# ESP32_Display_2_1_K__Main_V1_0.net
KiCad netlist of a schematic drawn in EAGLE
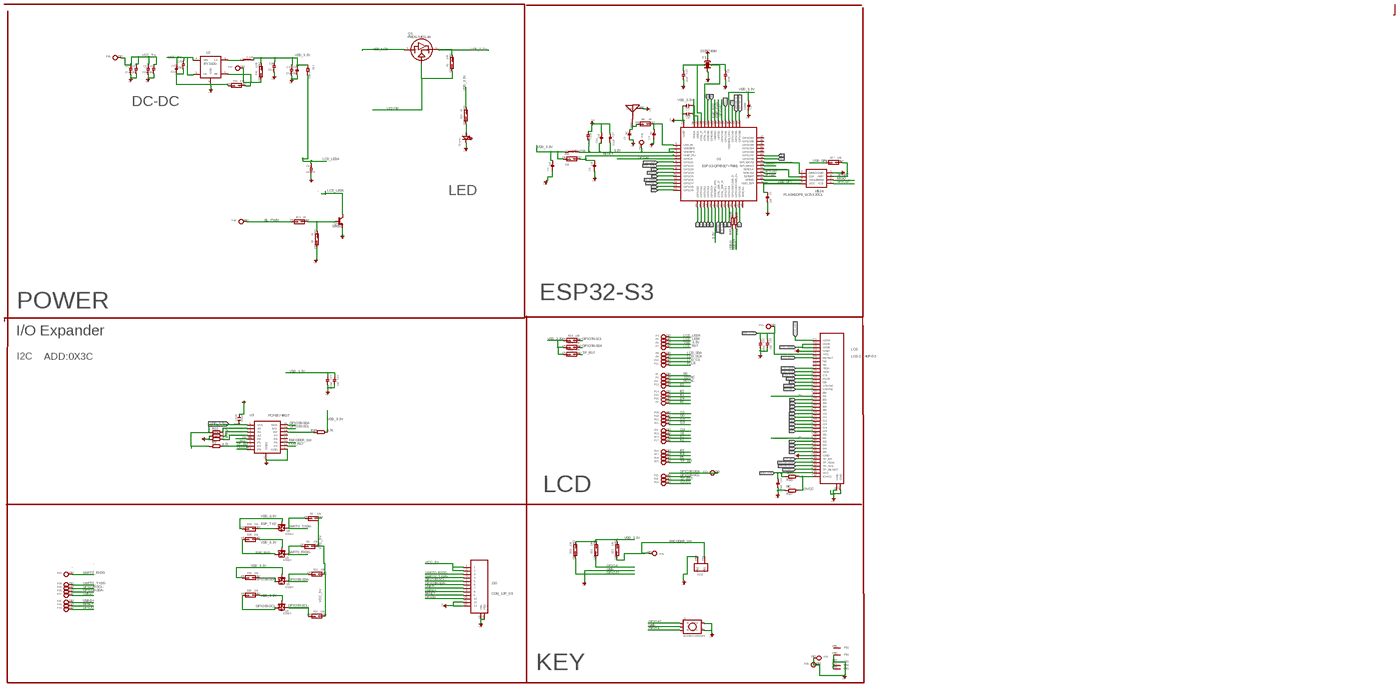
[diagram p0: schematic, sheet 1, overview]
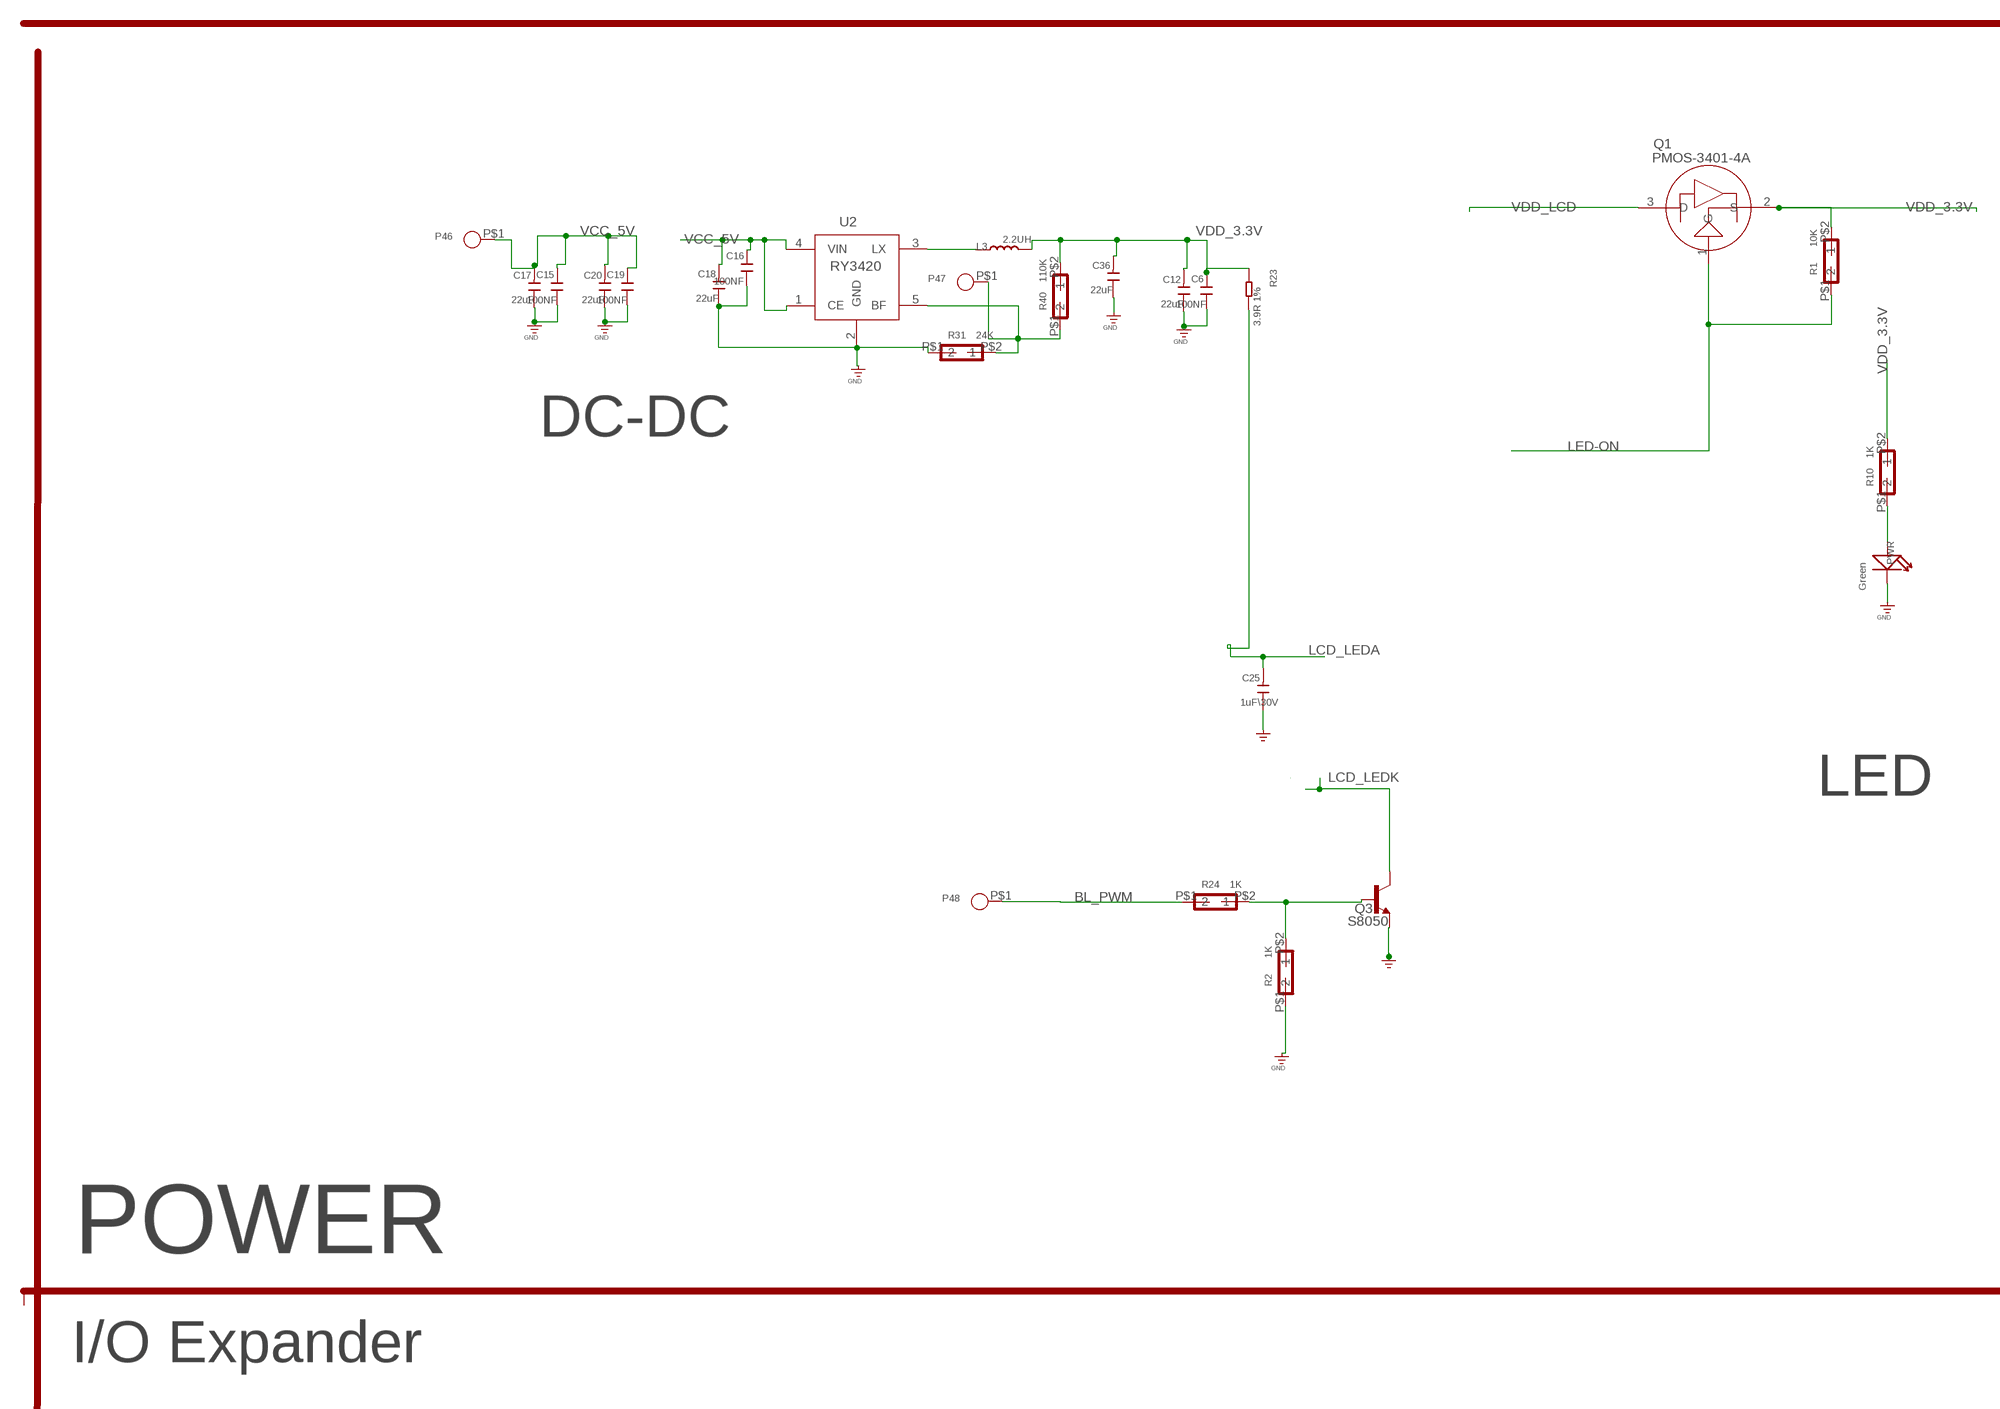
[diagram p1: schematic, sheet 1, part 1 of 5]
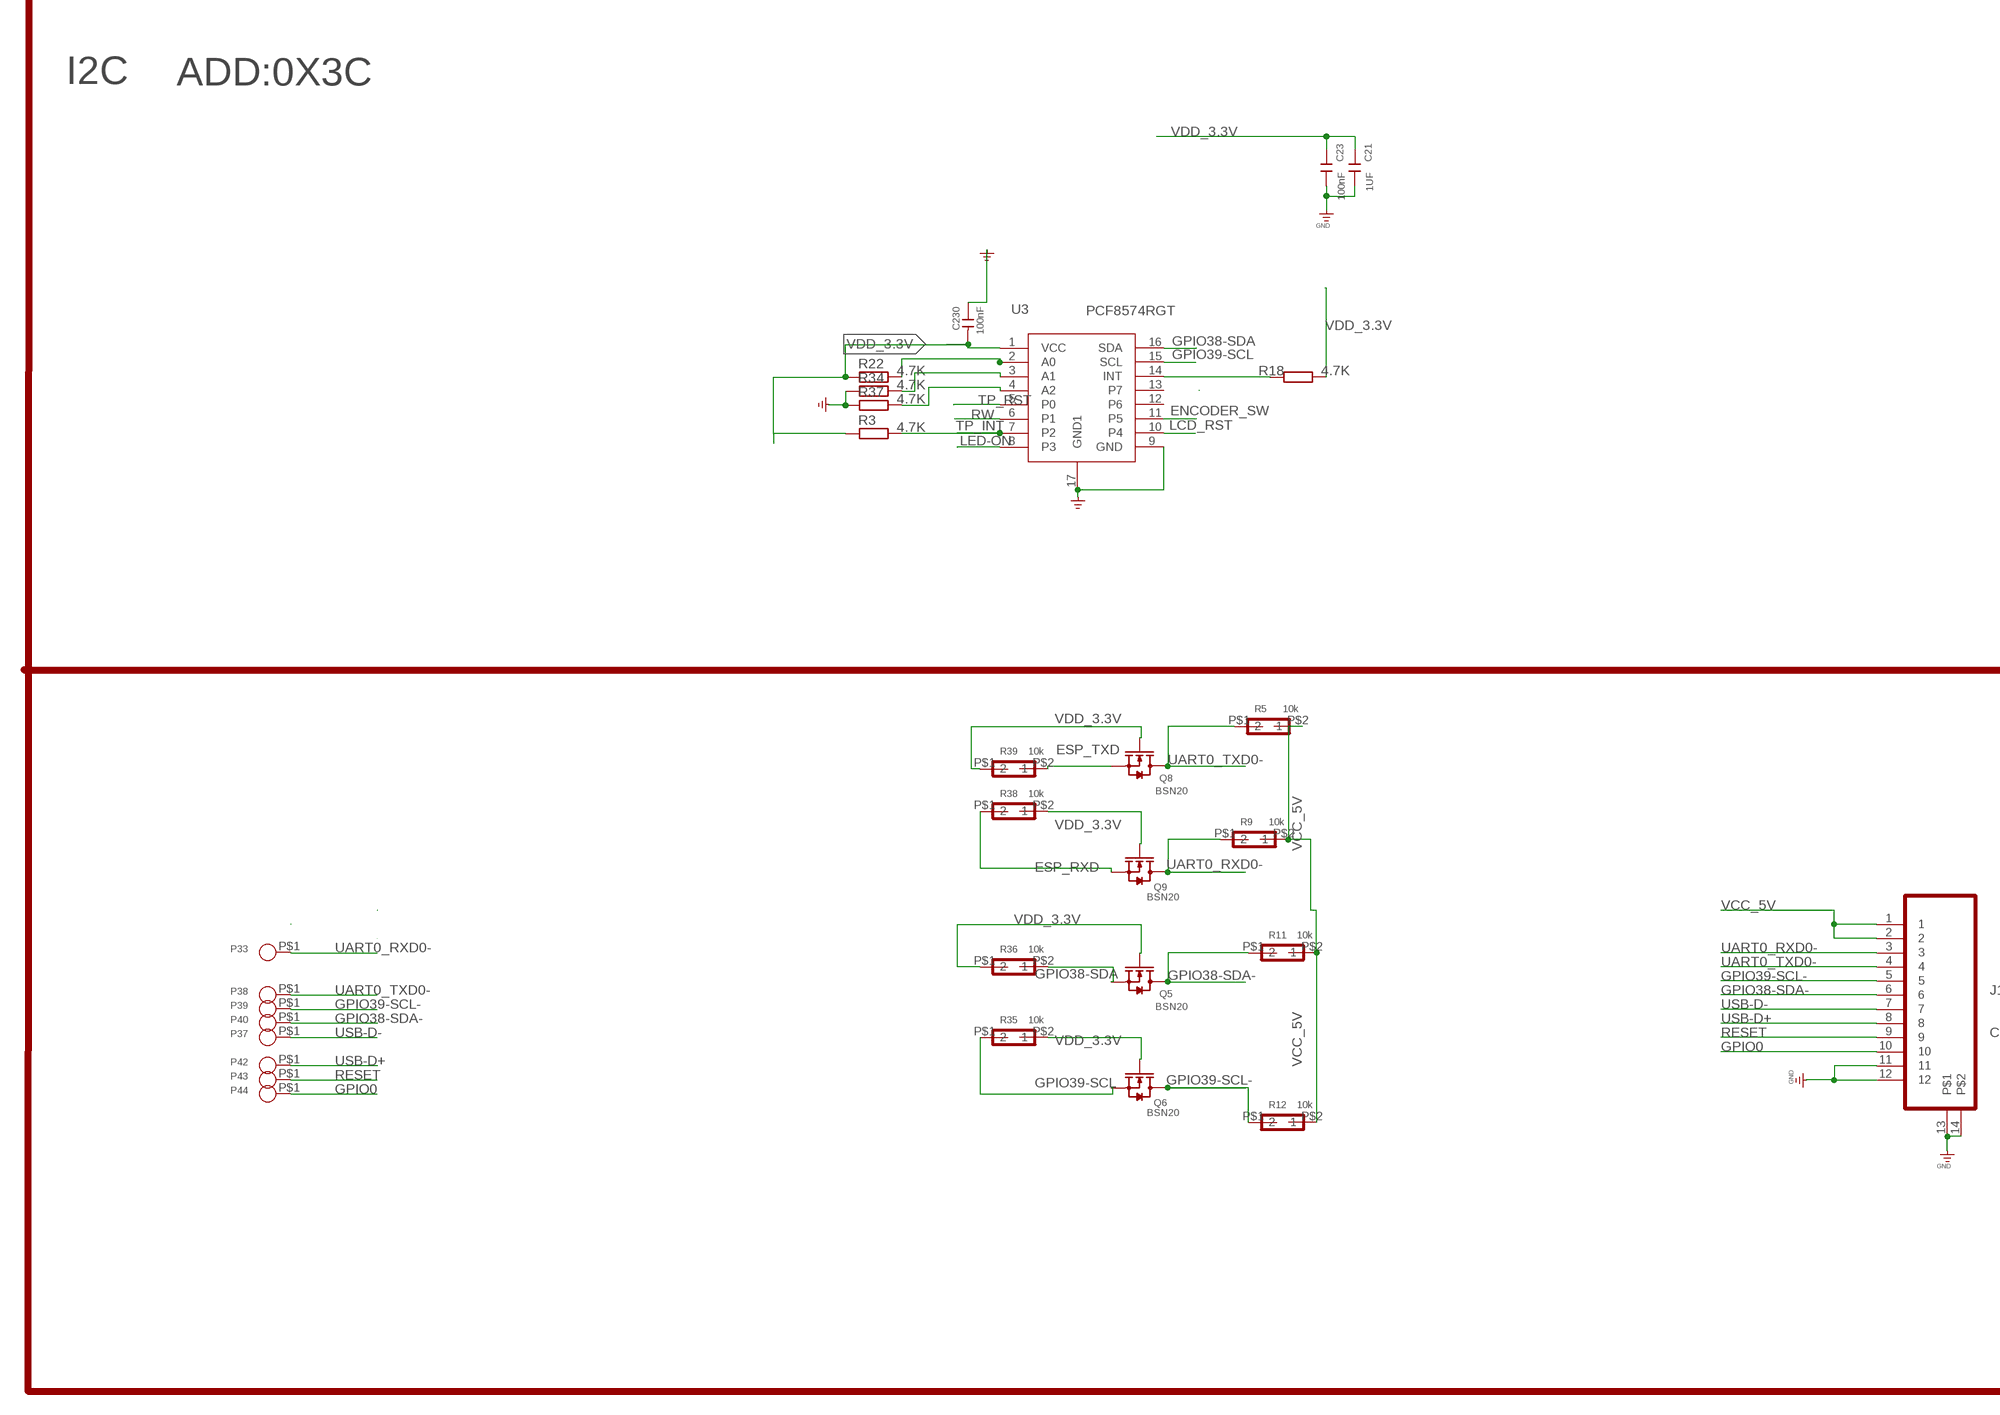
[diagram p2: schematic, sheet 1, part 2 of 5]
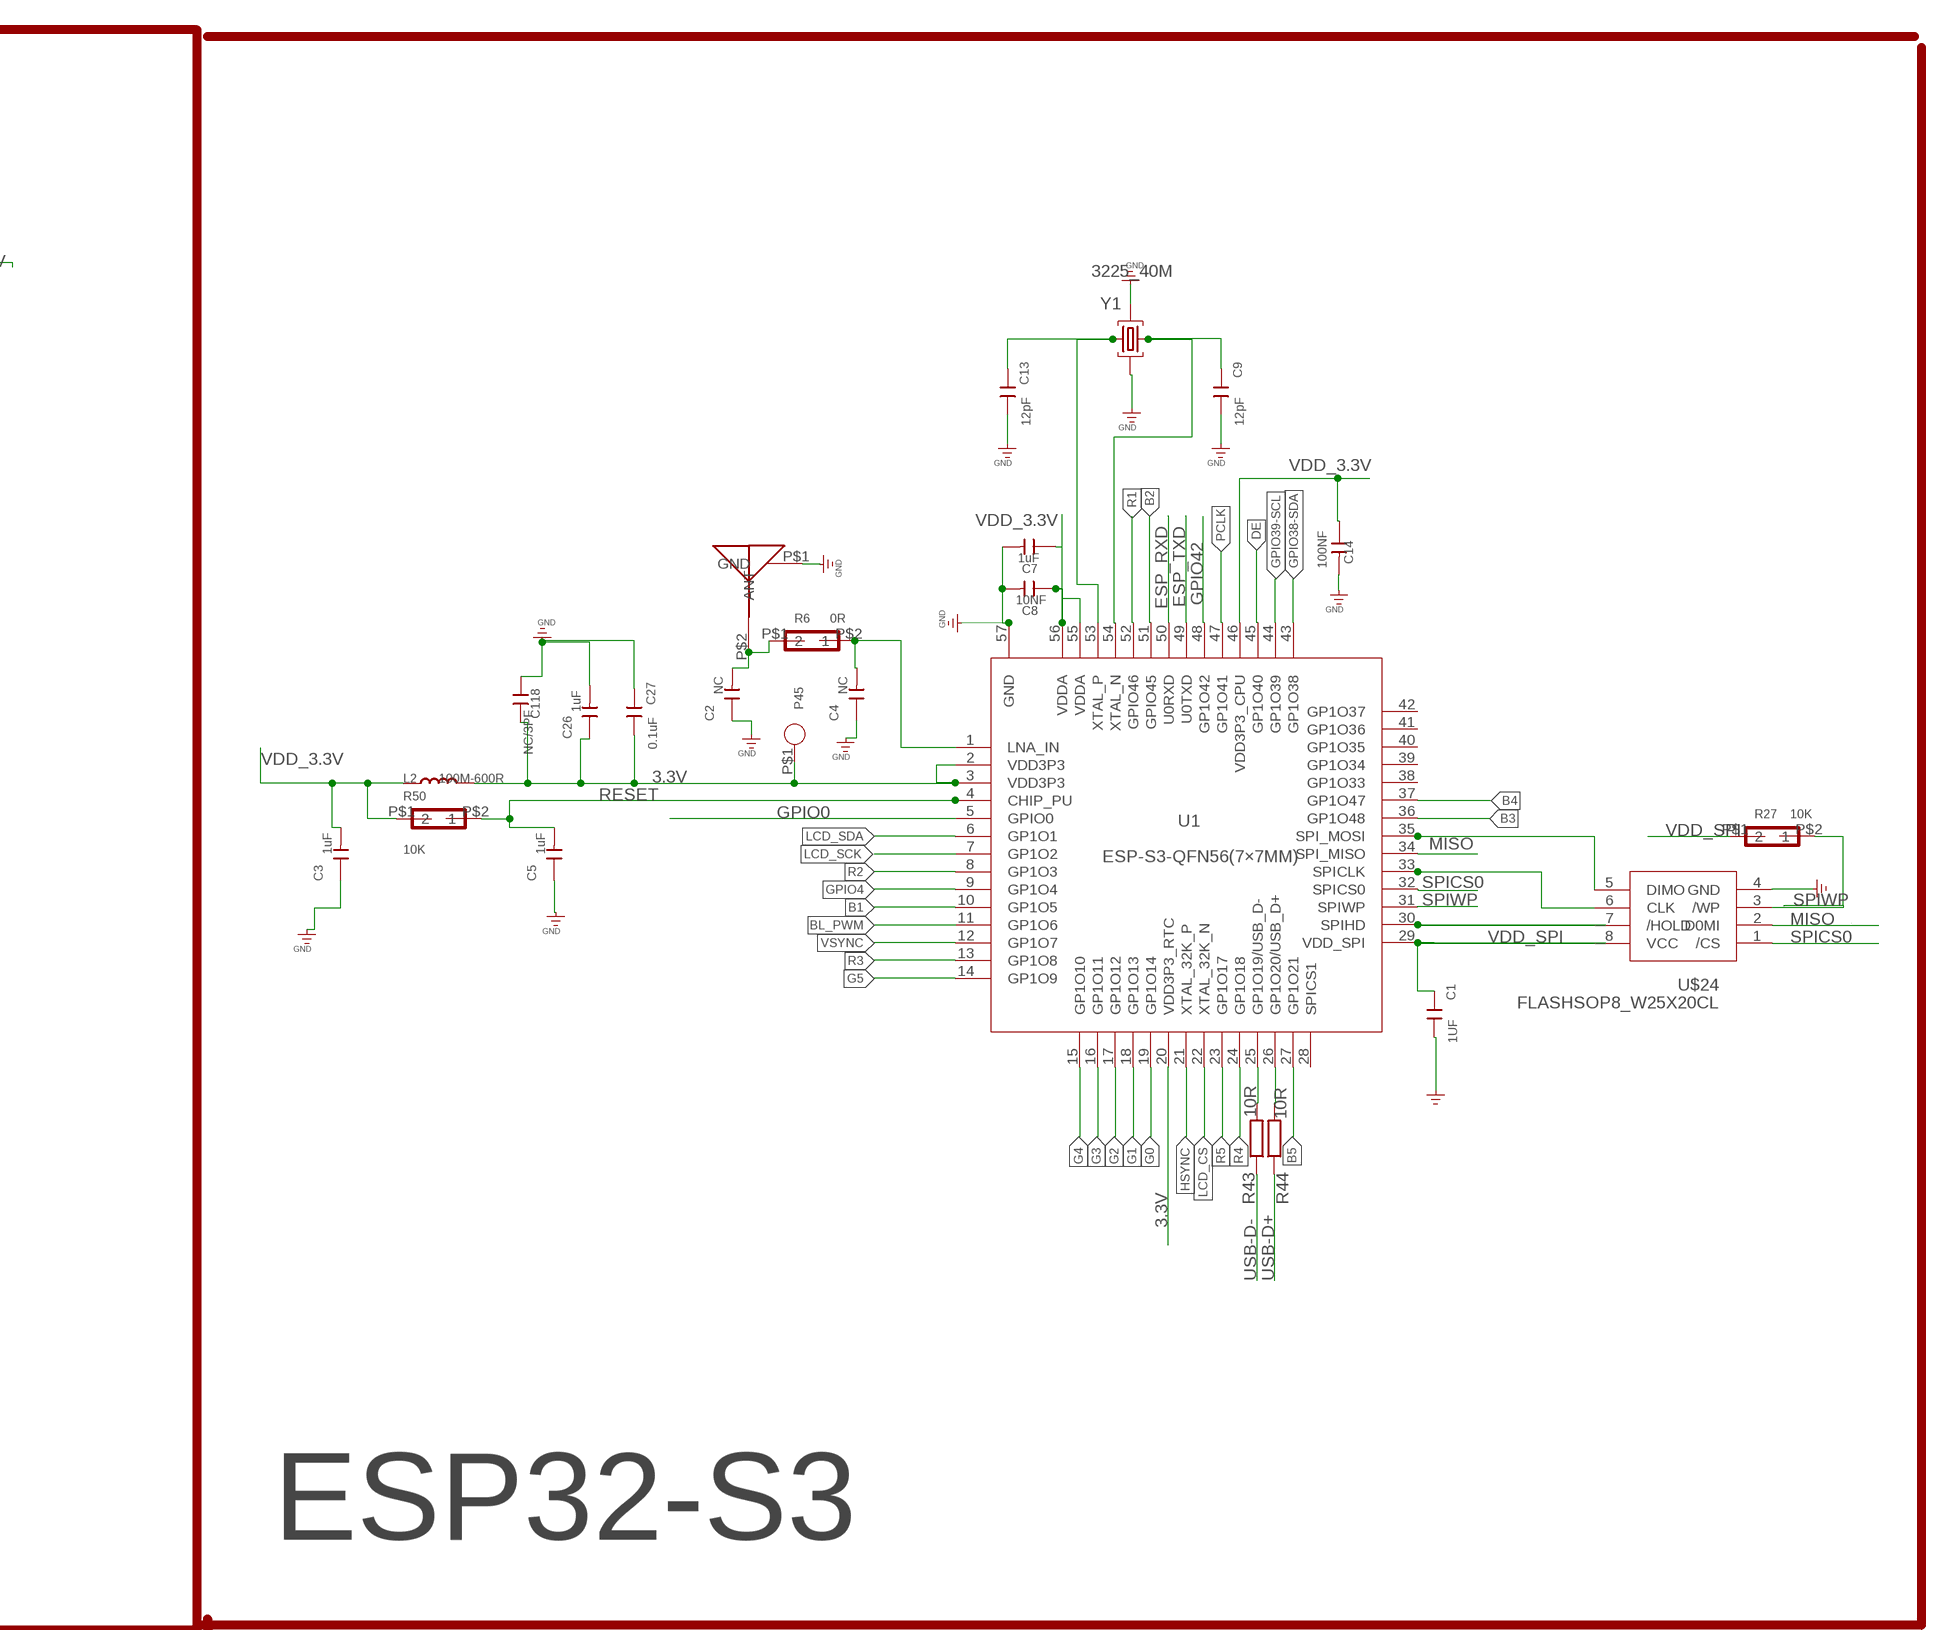
[diagram p3: schematic, sheet 1, part 3 of 5]
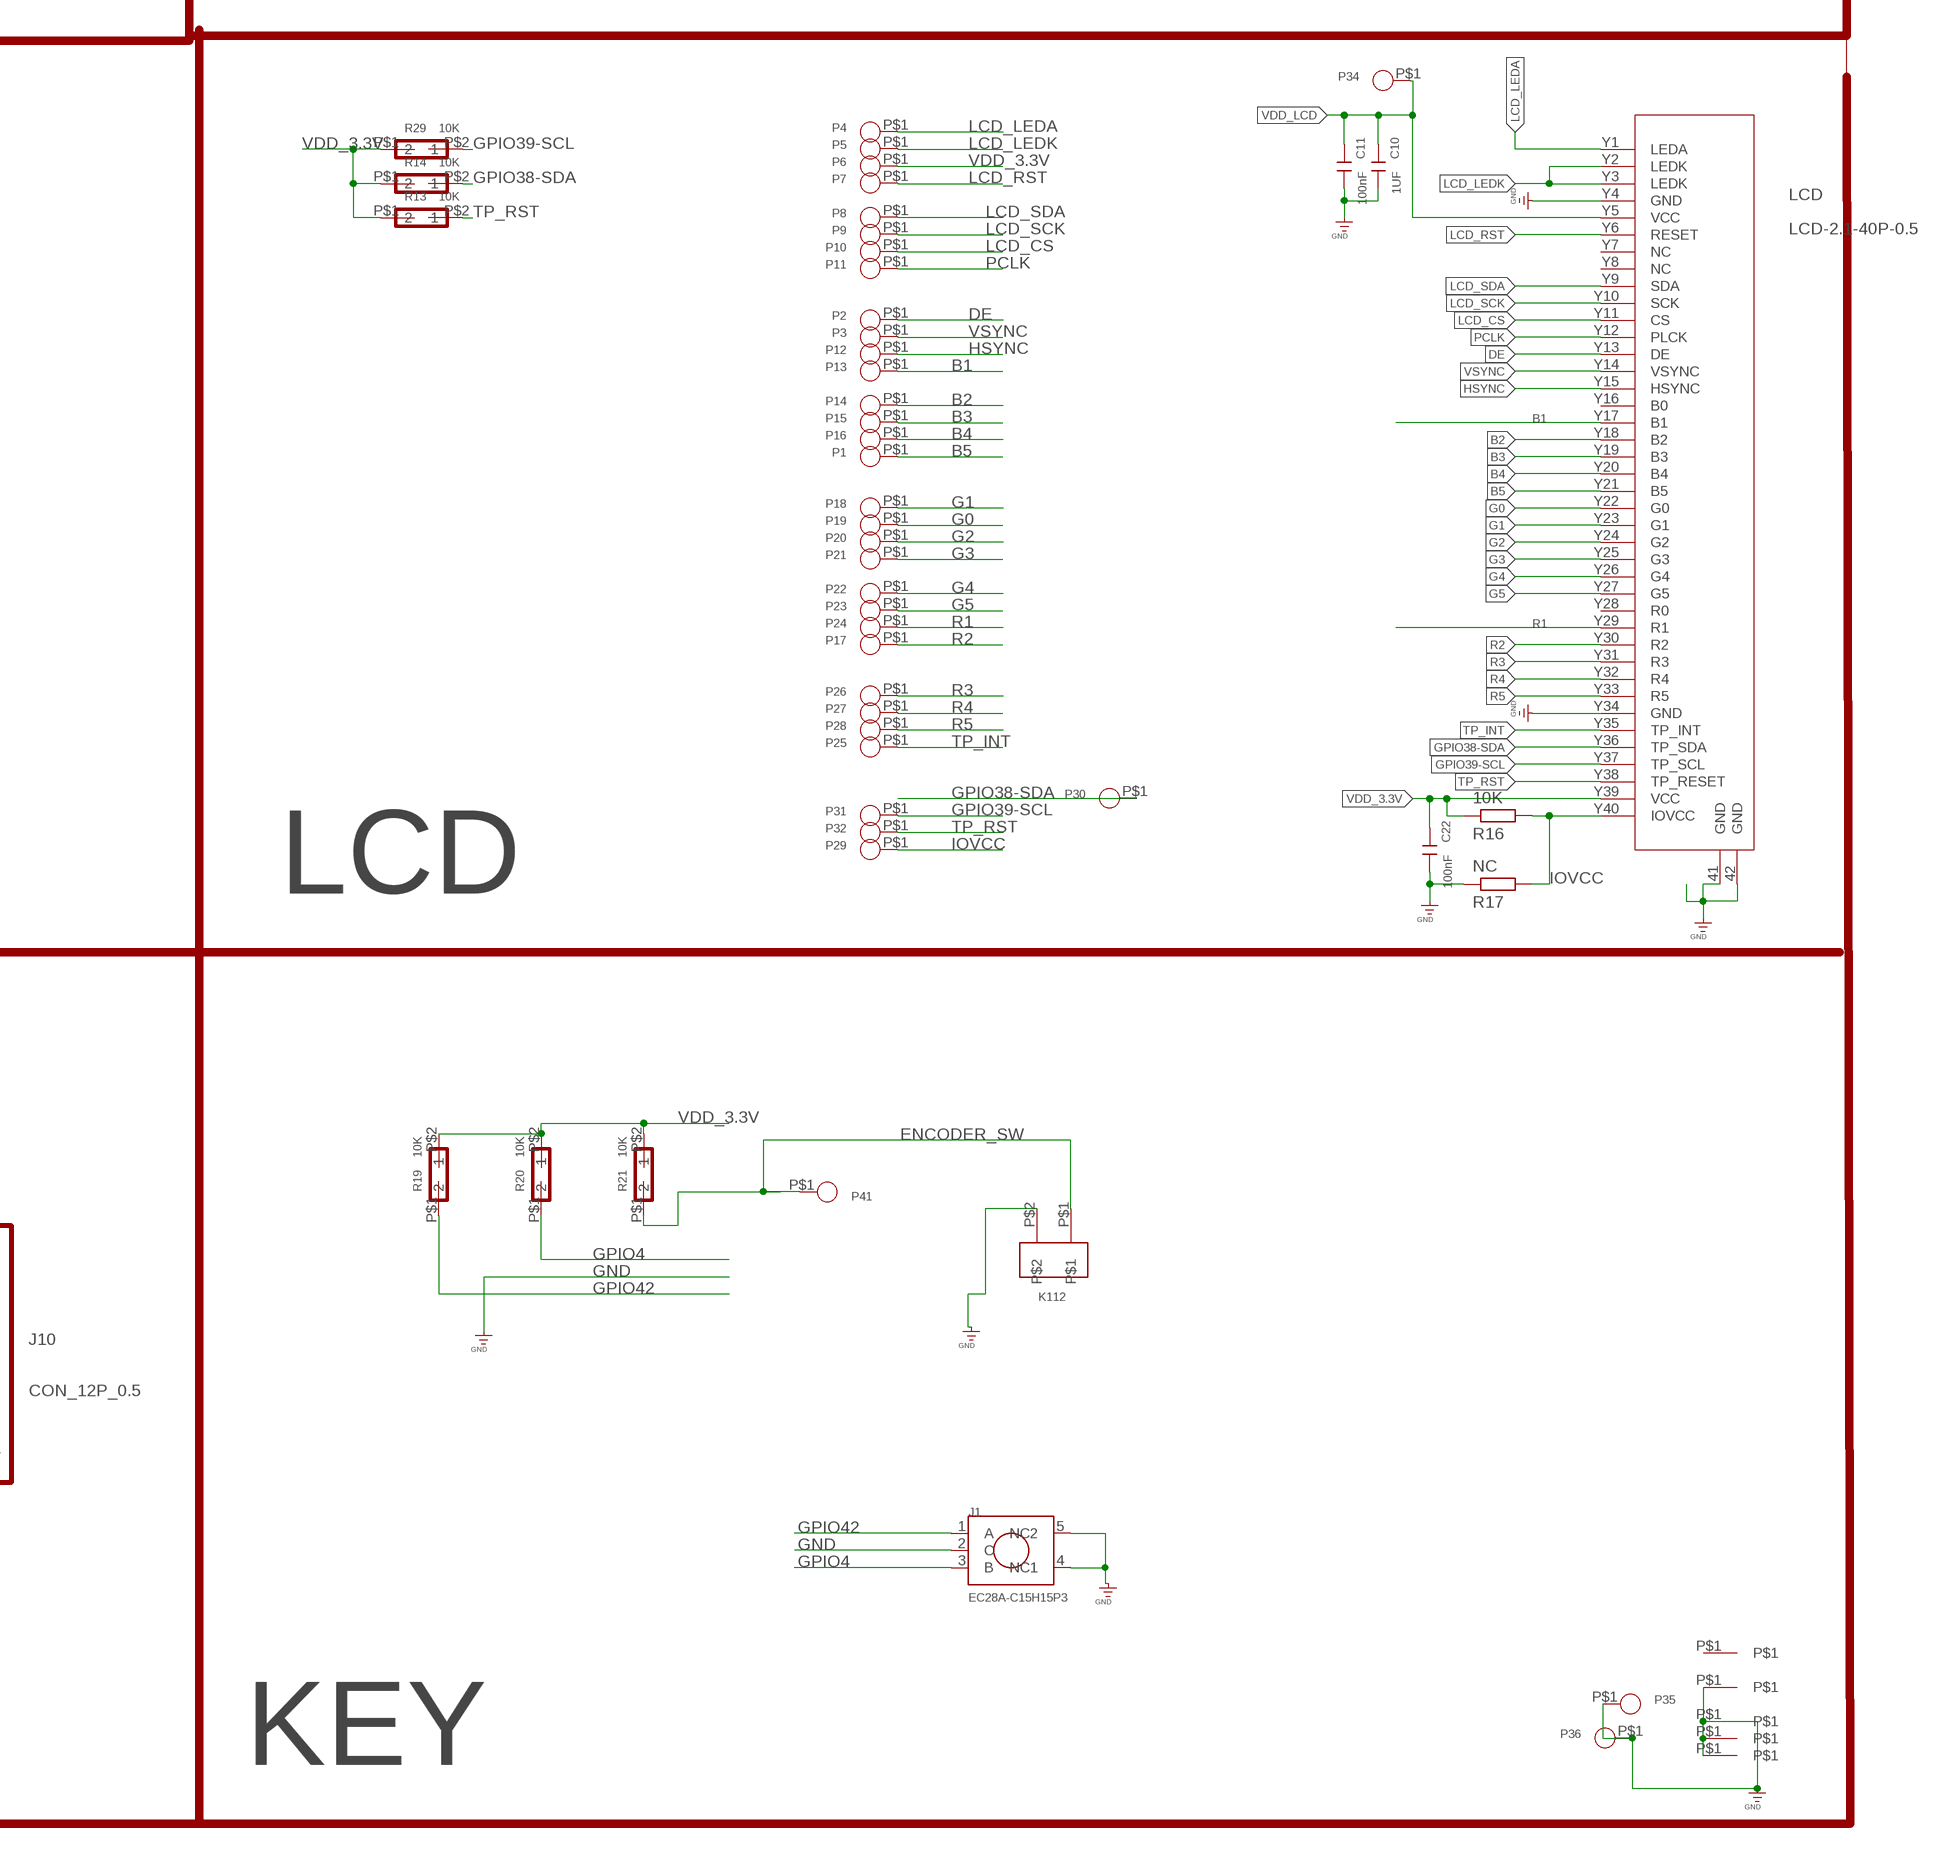
[diagram p4: schematic, sheet 1, part 4 of 5]
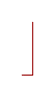
[diagram p5: schematic, sheet 1, part 5 of 5]

(export (version "E")
  (design (tool "Eeschema 10.0.6"))
  (components
    (comp (ref "ANT")
      (value "BT_ANT")
      (footprint "eagle-import:BT_ANT")
      (libsource (lib "eagle-import") (part "BT_ANT"))
    )
    (comp (ref "C1")
      (value "1UF")
      (footprint "eagle-import:0402")
      (libsource (lib "eagle-import") (part "C0402_W"))
    )
    (comp (ref "C2")
      (value "NC")
      (footprint "eagle-import:C0402")
      (libsource (lib "eagle-import") (part "CAPC0402-1"))
    )
    (comp (ref "C3")
      (value "1uF")
      (footprint "eagle-import:C0402")
      (libsource (lib "eagle-import") (part "CAPC0402-1"))
    )
    (comp (ref "C4")
      (value "NC")
      (footprint "eagle-import:C0402")
      (libsource (lib "eagle-import") (part "CAPC0402-1"))
    )
    (comp (ref "C5")
      (value "1uF")
      (footprint "eagle-import:C0402")
      (libsource (lib "eagle-import") (part "CAPC0402-1"))
    )
    (comp (ref "C6")
      (value "100NF")
      (footprint "eagle-import:0603")
      (libsource (lib "eagle-import") (part "C0603"))
    )
    (comp (ref "C7")
      (value "1uF")
      (footprint "eagle-import:C0603")
      (libsource (lib "eagle-import") (part "C-0603"))
    )
    (comp (ref "C8")
      (value "10NF")
      (footprint "eagle-import:C0603")
      (libsource (lib "eagle-import") (part "C-0603"))
    )
    (comp (ref "C9")
      (value "12pF")
      (footprint "eagle-import:0402")
      (libsource (lib "eagle-import") (part "C0402_W"))
    )
    (comp (ref "C10")
      (value "1UF")
      (footprint "eagle-import:0402")
      (libsource (lib "eagle-import") (part "C0402_W"))
    )
    (comp (ref "C11")
      (value "100nF")
      (footprint "eagle-import:0402")
      (libsource (lib "eagle-import") (part "C0402_W"))
    )
    (comp (ref "C12")
      (value "22uF")
      (footprint "eagle-import:0805")
      (libsource (lib "eagle-import") (part "C0805"))
    )
    (comp (ref "C13")
      (value "12pF")
      (footprint "eagle-import:0402")
      (libsource (lib "eagle-import") (part "C0402_W"))
    )
    (comp (ref "C14")
      (value "100NF")
      (footprint "eagle-import:C0603")
      (libsource (lib "eagle-import") (part "C-0603"))
    )
    (comp (ref "C15")
      (value "100NF")
      (footprint "eagle-import:0603")
      (libsource (lib "eagle-import") (part "C0603"))
    )
    (comp (ref "C16")
      (value "100NF")
      (footprint "eagle-import:0603")
      (libsource (lib "eagle-import") (part "C0603"))
    )
    (comp (ref "C17")
      (value "22uF")
      (footprint "eagle-import:0805")
      (libsource (lib "eagle-import") (part "C0805"))
    )
    (comp (ref "C18")
      (value "22uF")
      (footprint "eagle-import:0805")
      (libsource (lib "eagle-import") (part "C0805"))
    )
    (comp (ref "C19")
      (value "100NF")
      (footprint "eagle-import:0603")
      (libsource (lib "eagle-import") (part "C0603"))
    )
    (comp (ref "C20")
      (value "22uF")
      (footprint "eagle-import:0805")
      (libsource (lib "eagle-import") (part "C0805"))
    )
    (comp (ref "C21")
      (value "1UF")
      (footprint "eagle-import:0402")
      (libsource (lib "eagle-import") (part "C0402_W"))
    )
    (comp (ref "C22")
      (value "100nF")
      (footprint "eagle-import:0402")
      (libsource (lib "eagle-import") (part "C0402_W"))
    )
    (comp (ref "C23")
      (value "100nF")
      (footprint "eagle-import:0402")
      (libsource (lib "eagle-import") (part "C0402_W"))
    )
    (comp (ref "C25")
      (value "1uF\\30V")
      (footprint "eagle-import:0805")
      (libsource (lib "eagle-import") (part "C0805"))
    )
    (comp (ref "C26")
      (value "1uF")
      (footprint "eagle-import:C0402")
      (libsource (lib "eagle-import") (part "CAPC0402-1"))
    )
    (comp (ref "C27")
      (value "0.1uF")
      (footprint "eagle-import:0402")
      (libsource (lib "eagle-import") (part "C0402_W"))
    )
    (comp (ref "C36")
      (value "22uF")
      (footprint "eagle-import:0805")
      (libsource (lib "eagle-import") (part "C0805"))
    )
    (comp (ref "C118")
      (value "NC/3PF")
      (footprint "eagle-import:0603")
      (libsource (lib "eagle-import") (part "C0603"))
    )
    (comp (ref "C230")
      (value "100nF")
      (footprint "eagle-import:C0603")
      (libsource (lib "eagle-import") (part "CAPC0603"))
    )
    (comp (ref "J1")
      (value "EC28A-C15H15P3")
      (footprint "eagle-import:EC28A-C15H15P3")
      (libsource (lib "eagle-import") (part "EC28A-C15H15P3"))
    )
    (comp (ref "J10")
      (value "CON_12P_0.5")
      (footprint "eagle-import:0.5MM-12P")
      (libsource (lib "eagle-import") (part "CON_12P_0.5"))
    )
    (comp (ref "K112")
      (value "BUTTON_2P")
      (footprint "eagle-import:BUTTON_2P")
      (libsource (lib "eagle-import") (part "BUTTON_2P"))
    )
    (comp (ref "L2")
      (value "100M-600R")
      (footprint "eagle-import:L0603")
      (libsource (lib "eagle-import") (part "L0603"))
    )
    (comp (ref "L3")
      (value "2.2UH")
      (footprint "eagle-import:L0420")
      (libsource (lib "eagle-import") (part "LL0420"))
    )
    (comp (ref "LCD")
      (value "LCD-2.1-40P-0.5")
      (footprint "eagle-import:0.5MM-40P")
      (libsource (lib "eagle-import") (part "LCD-2.1-40P-0.5"))
    )
    (comp (ref "P1")
      (value "PADPAD-1.0MM")
      (footprint "eagle-import:PAD-1.0MM")
      (libsource (lib "eagle-import") (part "PADPAD-1.0MM"))
    )
    (comp (ref "P2")
      (value "PADPAD-1.0MM")
      (footprint "eagle-import:PAD-1.0MM")
      (libsource (lib "eagle-import") (part "PADPAD-1.0MM"))
    )
    (comp (ref "P3")
      (value "PADPAD-1.0MM")
      (footprint "eagle-import:PAD-1.0MM")
      (libsource (lib "eagle-import") (part "PADPAD-1.0MM"))
    )
    (comp (ref "P4")
      (value "PADPAD-1.0MM")
      (footprint "eagle-import:PAD-1.0MM")
      (libsource (lib "eagle-import") (part "PADPAD-1.0MM"))
    )
    (comp (ref "P5")
      (value "PADPAD-1.0MM")
      (footprint "eagle-import:PAD-1.0MM")
      (libsource (lib "eagle-import") (part "PADPAD-1.0MM"))
    )
    (comp (ref "P6")
      (value "PADPAD-1.0MM")
      (footprint "eagle-import:PAD-1.0MM")
      (libsource (lib "eagle-import") (part "PADPAD-1.0MM"))
    )
    (comp (ref "P7")
      (value "PADPAD-1.0MM")
      (footprint "eagle-import:PAD-1.0MM")
      (libsource (lib "eagle-import") (part "PADPAD-1.0MM"))
    )
    (comp (ref "P8")
      (value "PADPAD-1.0MM")
      (footprint "eagle-import:PAD-1.0MM")
      (libsource (lib "eagle-import") (part "PADPAD-1.0MM"))
    )
    (comp (ref "P9")
      (value "PADPAD-1.0MM")
      (footprint "eagle-import:PAD-1.0MM")
      (libsource (lib "eagle-import") (part "PADPAD-1.0MM"))
    )
    (comp (ref "P10")
      (value "PADPAD-1.0MM")
      (footprint "eagle-import:PAD-1.0MM")
      (libsource (lib "eagle-import") (part "PADPAD-1.0MM"))
    )
    (comp (ref "P11")
      (value "PADPAD-1.0MM")
      (footprint "eagle-import:PAD-1.0MM")
      (libsource (lib "eagle-import") (part "PADPAD-1.0MM"))
    )
    (comp (ref "P12")
      (value "PADPAD-1.0MM")
      (footprint "eagle-import:PAD-1.0MM")
      (libsource (lib "eagle-import") (part "PADPAD-1.0MM"))
    )
    (comp (ref "P13")
      (value "PADPAD-1.0MM")
      (footprint "eagle-import:PAD-1.0MM")
      (libsource (lib "eagle-import") (part "PADPAD-1.0MM"))
    )
    (comp (ref "P14")
      (value "PADPAD-1.0MM")
      (footprint "eagle-import:PAD-1.0MM")
      (libsource (lib "eagle-import") (part "PADPAD-1.0MM"))
    )
    (comp (ref "P15")
      (value "PADPAD-1.0MM")
      (footprint "eagle-import:PAD-1.0MM")
      (libsource (lib "eagle-import") (part "PADPAD-1.0MM"))
    )
    (comp (ref "P16")
      (value "PADPAD-1.0MM")
      (footprint "eagle-import:PAD-1.0MM")
      (libsource (lib "eagle-import") (part "PADPAD-1.0MM"))
    )
    (comp (ref "P17")
      (value "PADPAD-1.0MM")
      (footprint "eagle-import:PAD-1.0MM")
      (libsource (lib "eagle-import") (part "PADPAD-1.0MM"))
    )
    (comp (ref "P18")
      (value "PADPAD-1.0MM")
      (footprint "eagle-import:PAD-1.0MM")
      (libsource (lib "eagle-import") (part "PADPAD-1.0MM"))
    )
    (comp (ref "P19")
      (value "PADPAD-1.0MM")
      (footprint "eagle-import:PAD-1.0MM")
      (libsource (lib "eagle-import") (part "PADPAD-1.0MM"))
    )
    (comp (ref "P20")
      (value "PADPAD-1.0MM")
      (footprint "eagle-import:PAD-1.0MM")
      (libsource (lib "eagle-import") (part "PADPAD-1.0MM"))
    )
    (comp (ref "P21")
      (value "PADPAD-1.0MM")
      (footprint "eagle-import:PAD-1.0MM")
      (libsource (lib "eagle-import") (part "PADPAD-1.0MM"))
    )
    (comp (ref "P22")
      (value "PADPAD-1.0MM")
      (footprint "eagle-import:PAD-1.0MM")
      (libsource (lib "eagle-import") (part "PADPAD-1.0MM"))
    )
    (comp (ref "P23")
      (value "PADPAD-1.0MM")
      (footprint "eagle-import:PAD-1.0MM")
      (libsource (lib "eagle-import") (part "PADPAD-1.0MM"))
    )
    (comp (ref "P24")
      (value "PADPAD-1.0MM")
      (footprint "eagle-import:PAD-1.0MM")
      (libsource (lib "eagle-import") (part "PADPAD-1.0MM"))
    )
    (comp (ref "P25")
      (value "PADPAD-1.0MM")
      (footprint "eagle-import:PAD-1.0MM")
      (libsource (lib "eagle-import") (part "PADPAD-1.0MM"))
    )
    (comp (ref "P26")
      (value "PADPAD-1.0MM")
      (footprint "eagle-import:PAD-1.0MM")
      (libsource (lib "eagle-import") (part "PADPAD-1.0MM"))
    )
    (comp (ref "P27")
      (value "PADPAD-1.0MM")
      (footprint "eagle-import:PAD-1.0MM")
      (libsource (lib "eagle-import") (part "PADPAD-1.0MM"))
    )
    (comp (ref "P28")
      (value "PADPAD-1.0MM")
      (footprint "eagle-import:PAD-1.0MM")
      (libsource (lib "eagle-import") (part "PADPAD-1.0MM"))
    )
    (comp (ref "P29")
      (value "PADPAD-1.0MM")
      (footprint "eagle-import:PAD-1.0MM")
      (libsource (lib "eagle-import") (part "PADPAD-1.0MM"))
    )
    (comp (ref "P30")
      (value "PADPAD-1.0MM")
      (footprint "eagle-import:PAD-1.0MM")
      (libsource (lib "eagle-import") (part "PADPAD-1.0MM"))
    )
    (comp (ref "P31")
      (value "PADPAD-1.0MM")
      (footprint "eagle-import:PAD-1.0MM")
      (libsource (lib "eagle-import") (part "PADPAD-1.0MM"))
    )
    (comp (ref "P32")
      (value "PADPAD-1.0MM")
      (footprint "eagle-import:PAD-1.0MM")
      (libsource (lib "eagle-import") (part "PADPAD-1.0MM"))
    )
    (comp (ref "P33")
      (value "PADPAD-1.0MM")
      (footprint "eagle-import:PAD-1.0MM")
      (libsource (lib "eagle-import") (part "PADPAD-1.0MM"))
    )
    (comp (ref "P34")
      (value "PADPAD-1.0MM")
      (footprint "eagle-import:PAD-1.0MM")
      (libsource (lib "eagle-import") (part "PADPAD-1.0MM"))
    )
    (comp (ref "P35")
      (value "PADPAD-1.0MM")
      (footprint "eagle-import:PAD-1.0MM")
      (libsource (lib "eagle-import") (part "PADPAD-1.0MM"))
    )
    (comp (ref "P36")
      (value "PADPAD-1.0MM")
      (footprint "eagle-import:PAD-1.0MM")
      (libsource (lib "eagle-import") (part "PADPAD-1.0MM"))
    )
    (comp (ref "P37")
      (value "PADPAD-1.0MM")
      (footprint "eagle-import:PAD-1.0MM")
      (libsource (lib "eagle-import") (part "PADPAD-1.0MM"))
    )
    (comp (ref "P38")
      (value "PADPAD-1.0MM")
      (footprint "eagle-import:PAD-1.0MM")
      (libsource (lib "eagle-import") (part "PADPAD-1.0MM"))
    )
    (comp (ref "P39")
      (value "PADPAD-1.0MM")
      (footprint "eagle-import:PAD-1.0MM")
      (libsource (lib "eagle-import") (part "PADPAD-1.0MM"))
    )
    (comp (ref "P40")
      (value "PADPAD-1.0MM")
      (footprint "eagle-import:PAD-1.0MM")
      (libsource (lib "eagle-import") (part "PADPAD-1.0MM"))
    )
    (comp (ref "P41")
      (value "PADPAD-1.0MM")
      (footprint "eagle-import:PAD-1.0MM")
      (libsource (lib "eagle-import") (part "PADPAD-1.0MM"))
    )
    (comp (ref "P42")
      (value "PADPAD-1.0MM")
      (footprint "eagle-import:PAD-1.0MM")
      (libsource (lib "eagle-import") (part "PADPAD-1.0MM"))
    )
    (comp (ref "P43")
      (value "PADPAD-1.0MM")
      (footprint "eagle-import:PAD-1.0MM")
      (libsource (lib "eagle-import") (part "PADPAD-1.0MM"))
    )
    (comp (ref "P44")
      (value "PADPAD-1.0MM")
      (footprint "eagle-import:PAD-1.0MM")
      (libsource (lib "eagle-import") (part "PADPAD-1.0MM"))
    )
    (comp (ref "P45")
      (value "PADPAD-1.0MM")
      (footprint "eagle-import:PAD-1.0MM")
      (libsource (lib "eagle-import") (part "PADPAD-1.0MM"))
    )
    (comp (ref "P46")
      (value "PADPAD-1.0MM")
      (footprint "eagle-import:PAD-1.0MM")
      (libsource (lib "eagle-import") (part "PADPAD-1.0MM"))
    )
    (comp (ref "P47")
      (value "PADPAD-1.0MM")
      (footprint "eagle-import:PAD-1.0MM")
      (libsource (lib "eagle-import") (part "PADPAD-1.0MM"))
    )
    (comp (ref "P48")
      (value "PADPAD-1.0MM")
      (footprint "eagle-import:PAD-1.0MM")
      (libsource (lib "eagle-import") (part "PADPAD-1.0MM"))
    )
    (comp (ref "PWR")
      (value "Green")
      (footprint "eagle-import:LED-0603")
      (libsource (lib "eagle-import") (part "LED'0603'"))
    )
    (comp (ref "Q1")
      (value "PMOS-3401-4A")
      (footprint "eagle-import:SOT-23")
      (libsource (lib "eagle-import") (part "P-MOS-SOT23"))
    )
    (comp (ref "Q3")
      (value "S8050")
      (footprint "eagle-import:SPARKFUN_SOT23")
      (libsource (lib "eagle-import") (part "SPARKFUN_TRANSISTOR_NPNSOT23"))
    )
    (comp (ref "Q5")
      (value "BSN20")
      (footprint "eagle-import:SOT23")
      (libsource (lib "eagle-import") (part "MOSFET-N'SOT23'"))
    )
    (comp (ref "Q6")
      (value "BSN20")
      (footprint "eagle-import:SOT23")
      (libsource (lib "eagle-import") (part "MOSFET-N'SOT23'"))
    )
    (comp (ref "Q8")
      (value "BSN20")
      (footprint "eagle-import:SOT23")
      (libsource (lib "eagle-import") (part "MOSFET-N'SOT23'"))
    )
    (comp (ref "Q9")
      (value "BSN20")
      (footprint "eagle-import:SOT23")
      (libsource (lib "eagle-import") (part "MOSFET-N'SOT23'"))
    )
    (comp (ref "R1")
      (value "10K")
      (footprint "eagle-import:0402")
      (libsource (lib "eagle-import") (part "R0402"))
    )
    (comp (ref "R2")
      (value "1K")
      (footprint "eagle-import:0402")
      (libsource (lib "eagle-import") (part "R0402"))
    )
    (comp (ref "R3")
      (value "4.7K")
      (footprint "eagle-import:R0402")
      (libsource (lib "eagle-import") (part "R-EU_R0402"))
    )
    (comp (ref "R5")
      (value "10k")
      (footprint "eagle-import:0402")
      (libsource (lib "eagle-import") (part "R0402"))
    )
    (comp (ref "R6")
      (value "0R")
      (footprint "eagle-import:0402")
      (libsource (lib "eagle-import") (part "R0402"))
    )
    (comp (ref "R9")
      (value "10k")
      (footprint "eagle-import:0402")
      (libsource (lib "eagle-import") (part "R0402"))
    )
    (comp (ref "R10")
      (value "1K")
      (footprint "eagle-import:0402")
      (libsource (lib "eagle-import") (part "R0402"))
    )
    (comp (ref "R11")
      (value "10k")
      (footprint "eagle-import:0402")
      (libsource (lib "eagle-import") (part "R0402"))
    )
    (comp (ref "R12")
      (value "10k")
      (footprint "eagle-import:0402")
      (libsource (lib "eagle-import") (part "R0402"))
    )
    (comp (ref "R13")
      (value "10K")
      (footprint "eagle-import:0402")
      (libsource (lib "eagle-import") (part "R0402"))
    )
    (comp (ref "R14")
      (value "10K")
      (footprint "eagle-import:0402")
      (libsource (lib "eagle-import") (part "R0402"))
    )
    (comp (ref "R16")
      (value "10K")
      (footprint "eagle-import:R0402")
      (libsource (lib "eagle-import") (part "R-EU_R0402"))
    )
    (comp (ref "R17")
      (value "NC")
      (footprint "eagle-import:R0402")
      (libsource (lib "eagle-import") (part "R-EU_R0402"))
    )
    (comp (ref "R18")
      (value "4.7K")
      (footprint "eagle-import:R0402")
      (libsource (lib "eagle-import") (part "R-EU_R0402"))
    )
    (comp (ref "R19")
      (value "10K")
      (footprint "eagle-import:0402")
      (libsource (lib "eagle-import") (part "R0402"))
    )
    (comp (ref "R20")
      (value "10K")
      (footprint "eagle-import:0402")
      (libsource (lib "eagle-import") (part "R0402"))
    )
    (comp (ref "R21")
      (value "10K")
      (footprint "eagle-import:0402")
      (libsource (lib "eagle-import") (part "R0402"))
    )
    (comp (ref "R22")
      (value "4.7K")
      (footprint "eagle-import:R0402")
      (libsource (lib "eagle-import") (part "R-EU_R0402"))
    )
    (comp (ref "R23")
      (value "3.9R 1%")
      (footprint "eagle-import:DISCRETE_R0603")
      (libsource (lib "eagle-import") (part "DISCRETE_R-0603"))
    )
    (comp (ref "R24")
      (value "1K")
      (footprint "eagle-import:0402")
      (libsource (lib "eagle-import") (part "R0402"))
    )
    (comp (ref "R27")
      (value "10K")
      (footprint "eagle-import:0402")
      (libsource (lib "eagle-import") (part "R0402"))
    )
    (comp (ref "R29")
      (value "10K")
      (footprint "eagle-import:0402")
      (libsource (lib "eagle-import") (part "R0402"))
    )
    (comp (ref "R31")
      (value "24K")
      (footprint "eagle-import:0402")
      (libsource (lib "eagle-import") (part "R0402"))
    )
    (comp (ref "R34")
      (value "4.7K")
      (footprint "eagle-import:R0402")
      (libsource (lib "eagle-import") (part "R-EU_R0402"))
    )
    (comp (ref "R35")
      (value "10k")
      (footprint "eagle-import:0402")
      (libsource (lib "eagle-import") (part "R0402"))
    )
    (comp (ref "R36")
      (value "10k")
      (footprint "eagle-import:0402")
      (libsource (lib "eagle-import") (part "R0402"))
    )
    (comp (ref "R37")
      (value "4.7K")
      (footprint "eagle-import:R0402")
      (libsource (lib "eagle-import") (part "R-EU_R0402"))
    )
    (comp (ref "R38")
      (value "10k")
      (footprint "eagle-import:0402")
      (libsource (lib "eagle-import") (part "R0402"))
    )
    (comp (ref "R39")
      (value "10k")
      (footprint "eagle-import:0402")
      (libsource (lib "eagle-import") (part "R0402"))
    )
    (comp (ref "R40")
      (value "110K")
      (footprint "eagle-import:0402")
      (libsource (lib "eagle-import") (part "R0402"))
    )
    (comp (ref "R43")
      (value "10R")
      (footprint "eagle-import:R0402")
      (libsource (lib "eagle-import") (part "R-EU_R0402"))
    )
    (comp (ref "R44")
      (value "10R")
      (footprint "eagle-import:R0402")
      (libsource (lib "eagle-import") (part "R-EU_R0402"))
    )
    (comp (ref "R50")
      (value "10K")
      (footprint "eagle-import:0402")
      (libsource (lib "eagle-import") (part "R0402"))
    )
    (comp (ref "U$9")
      (value "T-2-1.1")
      (footprint "eagle-import:T-2-1.1")
      (libsource (lib "eagle-import") (part "T-2-1.1"))
    )
    (comp (ref "U$19")
      (value "T-2-1.1")
      (footprint "eagle-import:T-2-1.1")
      (libsource (lib "eagle-import") (part "T-2-1.1"))
    )
    (comp (ref "U$24")
      (value "FLASHSOP8_W25X20CL")
      (footprint "eagle-import:FLASHSOP8_SOP8")
      (libsource (lib "eagle-import") (part "FLASHSOP8_W25X20CL"))
    )
    (comp (ref "U$29")
      (value "T-2-1.1")
      (footprint "eagle-import:T-2-1.1")
      (libsource (lib "eagle-import") (part "T-2-1.1"))
    )
    (comp (ref "U$30")
      (value "T-2-1.1")
      (footprint "eagle-import:T-2-1.1")
      (libsource (lib "eagle-import") (part "T-2-1.1"))
    )
    (comp (ref "U$32")
      (value "T-2-1.1")
      (footprint "eagle-import:T-2-1.1")
      (libsource (lib "eagle-import") (part "T-2-1.1"))
    )
    (comp (ref "U1")
      (value "ESP-S3-QFN56(7×7MM)")
      (footprint "eagle-import:ESP-S3-QFN56(7×7MM)")
      (libsource (lib "eagle-import") (part "ESP-S3-QFN56(7×7MM)"))
    )
    (comp (ref "U2")
      (value "RY3420")
      (footprint "eagle-import:SOT23-5")
      (libsource (lib "eagle-import") (part "HX3406"))
    )
    (comp (ref "U3")
      (value "PCF8574RGT")
      (footprint "eagle-import:QFN16-3_3")
      (libsource (lib "eagle-import") (part "PCF8574RGT"))
    )
    (comp (ref "Y1")
      (value "3225_40M")
      (footprint "eagle-import:CRYSTAL-3.2-2.5")
      (libsource (lib "eagle-import") (part "CRYSTAL-3.2-2.5"))
    )
  )
  (nets
    (net (code "1") (name "/3.3V") (class "Default")
      (node (ref "C118") (pin "2") (pinfunction "2_2") (pintype "passive"))
      (node (ref "C26") (pin "1") (pinfunction "1_1") (pintype "passive"))
      (node (ref "C27") (pin "2") (pinfunction "2_2") (pintype "passive"))
      (node (ref "L2") (pin "2") (pinfunction "2_2") (pintype "passive"))
      (node (ref "P45") (pin "P$1") (pinfunction "P$1_P$1") (pintype "bidirectional"))
      (node (ref "U1") (pin "2") (pinfunction "VDD3P3_2") (pintype "bidirectional"))
      (node (ref "U1") (pin "20") (pinfunction "VDD3P3_RTC_20") (pintype "bidirectional"))
      (node (ref "U1") (pin "3") (pinfunction "VDD3P3_3") (pintype "bidirectional"))
    )
    (net (code "2") (name "/ENCODER_SW") (class "Default")
      (node (ref "K112") (pin "P$1") (pinfunction "P$1_P$1") (pintype "bidirectional"))
      (node (ref "P41") (pin "P$1") (pinfunction "P$1_P$1") (pintype "bidirectional"))
      (node (ref "R21") (pin "P$1") (pinfunction "1_P$1") (pintype "bidirectional"))
      (node (ref "U3") (pin "11") (pinfunction "P5_11") (pintype "bidirectional"))
    )
    (net (code "3") (name "/ESP_RXD") (class "Default")
      (node (ref "Q9") (pin "2") (pinfunction "S_2") (pintype "passive"))
      (node (ref "R38") (pin "P$1") (pinfunction "1_P$1") (pintype "bidirectional"))
      (node (ref "U1") (pin "50") (pinfunction "U0RXD_50") (pintype "bidirectional"))
    )
    (net (code "4") (name "/ESP_TXD") (class "Default")
      (node (ref "Q8") (pin "2") (pinfunction "S_2") (pintype "passive"))
      (node (ref "R39") (pin "P$2") (pinfunction "2_P$2") (pintype "bidirectional"))
      (node (ref "U1") (pin "49") (pinfunction "U0TXD_49") (pintype "bidirectional"))
    )
    (net (code "5") (name "/GPIO0") (class "Default")
      (node (ref "J10") (pin "10") (pinfunction "10_10") (pintype "bidirectional"))
      (node (ref "P44") (pin "P$1") (pinfunction "P$1_P$1") (pintype "bidirectional"))
      (node (ref "U1") (pin "5") (pinfunction "GPIO0_5") (pintype "bidirectional"))
    )
    (net (code "6") (name "/GPIO38-SDA-") (class "Default")
      (node (ref "J10") (pin "6") (pinfunction "6_6") (pintype "bidirectional"))
      (node (ref "P40") (pin "P$1") (pinfunction "P$1_P$1") (pintype "bidirectional"))
      (node (ref "Q5") (pin "3") (pinfunction "D_3") (pintype "passive"))
      (node (ref "R11") (pin "P$1") (pinfunction "1_P$1") (pintype "bidirectional"))
    )
    (net (code "7") (name "/GPIO39-SCL-") (class "Default")
      (node (ref "J10") (pin "5") (pinfunction "5_5") (pintype "bidirectional"))
      (node (ref "P39") (pin "P$1") (pinfunction "P$1_P$1") (pintype "bidirectional"))
      (node (ref "Q6") (pin "3") (pinfunction "D_3") (pintype "passive"))
      (node (ref "R12") (pin "P$1") (pinfunction "1_P$1") (pintype "bidirectional"))
    )
    (net (code "8") (name "/GPIO42") (class "Default")
      (node (ref "J1") (pin "1") (pinfunction "A_1") (pintype "bidirectional"))
      (node (ref "R19") (pin "P$1") (pinfunction "1_P$1") (pintype "bidirectional"))
      (node (ref "U1") (pin "48") (pinfunction "GP1O42_48") (pintype "bidirectional"))
    )
    (net (code "9") (name "/IOVCC") (class "Default")
      (node (ref "LCD") (pin "Y40") (pinfunction "IOVCC_Y40") (pintype "bidirectional"))
      (node (ref "P29") (pin "P$1") (pinfunction "P$1_P$1") (pintype "bidirectional"))
      (node (ref "R16") (pin "1") (pinfunction "1_1") (pintype "passive"))
      (node (ref "R17") (pin "1") (pinfunction "1_1") (pintype "passive"))
    )
    (net (code "10") (name "/LED-ON") (class "Default")
      (node (ref "Q1") (pin "1") (pinfunction "G_1") (pintype "bidirectional"))
      (node (ref "R1") (pin "P$1") (pinfunction "1_P$1") (pintype "bidirectional"))
      (node (ref "U3") (pin "8") (pinfunction "P3_8") (pintype "bidirectional"))
    )
    (net (code "11") (name "/MISO") (class "Default")
      (node (ref "U$24") (pin "2") (pinfunction "D0MI_2") (pintype "output"))
      (node (ref "U1") (pin "34") (pinfunction "SPI_MISO_34") (pintype "bidirectional"))
    )
    (net (code "12") (name "/RESET") (class "Default")
      (node (ref "C5") (pin "2") (pinfunction "2_2") (pintype "passive"))
      (node (ref "J10") (pin "9") (pinfunction "9_9") (pintype "bidirectional"))
      (node (ref "P43") (pin "P$1") (pinfunction "P$1_P$1") (pintype "bidirectional"))
      (node (ref "R50") (pin "P$2") (pinfunction "2_P$2") (pintype "bidirectional"))
      (node (ref "U1") (pin "4") (pinfunction "CHIP_PU_4") (pintype "bidirectional"))
    )
    (net (code "13") (name "/RW") (class "Default")
      (node (ref "U3") (pin "6") (pinfunction "P1_6") (pintype "bidirectional"))
    )
    (net (code "14") (name "/SPICS0") (class "Default")
      (node (ref "U$24") (pin "1") (pinfunction "/CS_1") (pintype "bidirectional"))
      (node (ref "U1") (pin "32") (pinfunction "SPICS0_32") (pintype "bidirectional"))
    )
    (net (code "15") (name "/SPIWP") (class "Default")
      (node (ref "R27") (pin "P$2") (pinfunction "2_P$2") (pintype "bidirectional"))
      (node (ref "U$24") (pin "3") (pinfunction "/WP_3") (pintype "bidirectional"))
      (node (ref "U1") (pin "31") (pinfunction "SPIWP_31") (pintype "bidirectional"))
    )
    (net (code "16") (name "/UART0_RXD0-") (class "Default")
      (node (ref "J10") (pin "3") (pinfunction "3_3") (pintype "bidirectional"))
      (node (ref "P33") (pin "P$1") (pinfunction "P$1_P$1") (pintype "bidirectional"))
      (node (ref "Q9") (pin "3") (pinfunction "D_3") (pintype "passive"))
      (node (ref "R9") (pin "P$1") (pinfunction "1_P$1") (pintype "bidirectional"))
    )
    (net (code "17") (name "/UART0_TXD0-") (class "Default")
      (node (ref "J10") (pin "4") (pinfunction "4_4") (pintype "bidirectional"))
      (node (ref "P38") (pin "P$1") (pinfunction "P$1_P$1") (pintype "bidirectional"))
      (node (ref "Q8") (pin "3") (pinfunction "D_3") (pintype "passive"))
      (node (ref "R5") (pin "P$1") (pinfunction "1_P$1") (pintype "bidirectional"))
    )
    (net (code "18") (name "/USB-D+") (class "Default")
      (node (ref "J10") (pin "8") (pinfunction "8_8") (pintype "bidirectional"))
      (node (ref "P42") (pin "P$1") (pinfunction "P$1_P$1") (pintype "bidirectional"))
      (node (ref "R44") (pin "1") (pinfunction "1_1") (pintype "passive"))
    )
    (net (code "19") (name "/USB-D-") (class "Default")
      (node (ref "J10") (pin "7") (pinfunction "7_7") (pintype "bidirectional"))
      (node (ref "P37") (pin "P$1") (pinfunction "P$1_P$1") (pintype "bidirectional"))
      (node (ref "R43") (pin "1") (pinfunction "1_1") (pintype "passive"))
    )
    (net (code "20") (name "/VCC_5V") (class "Default")
      (node (ref "C15") (pin "1") (pinfunction "1_1") (pintype "passive"))
      (node (ref "C16") (pin "1") (pinfunction "1_1") (pintype "passive"))
      (node (ref "C17") (pin "2") (pinfunction "2_2") (pintype "passive"))
      (node (ref "C18") (pin "2") (pinfunction "2_2") (pintype "passive"))
      (node (ref "C19") (pin "1") (pinfunction "1_1") (pintype "passive"))
      (node (ref "C20") (pin "2") (pinfunction "2_2") (pintype "passive"))
      (node (ref "J10") (pin "1") (pinfunction "1_1") (pintype "bidirectional"))
      (node (ref "J10") (pin "2") (pinfunction "2_2") (pintype "bidirectional"))
      (node (ref "P46") (pin "P$1") (pinfunction "P$1_P$1") (pintype "bidirectional"))
      (node (ref "R11") (pin "P$2") (pinfunction "2_P$2") (pintype "bidirectional"))
      (node (ref "R12") (pin "P$2") (pinfunction "2_P$2") (pintype "bidirectional"))
      (node (ref "R5") (pin "P$2") (pinfunction "2_P$2") (pintype "bidirectional"))
      (node (ref "R9") (pin "P$2") (pinfunction "2_P$2") (pintype "bidirectional"))
      (node (ref "U2") (pin "1") (pinfunction "CE_1") (pintype "bidirectional"))
      (node (ref "U2") (pin "4") (pinfunction "VIN_4") (pintype "bidirectional"))
    )
    (net (code "21") (name "/VDD_SPI") (class "Default")
      (node (ref "C1") (pin "1") (pinfunction "1_1") (pintype "passive"))
      (node (ref "R27") (pin "P$1") (pinfunction "1_P$1") (pintype "bidirectional"))
      (node (ref "U$24") (pin "8") (pinfunction "VCC_8") (pintype "power_in"))
      (node (ref "U1") (pin "29") (pinfunction "VDD_SPI_29") (pintype "bidirectional"))
    )
    (net (code "22") (name "B1") (class "Default")
      (node (ref "LCD") (pin "Y17") (pinfunction "B1_Y17") (pintype "bidirectional"))
      (node (ref "P13") (pin "P$1") (pinfunction "P$1_P$1") (pintype "bidirectional"))
      (node (ref "U1") (pin "10") (pinfunction "GP1O5_10") (pintype "bidirectional"))
    )
    (net (code "23") (name "B2") (class "Default")
      (node (ref "LCD") (pin "Y18") (pinfunction "B2_Y18") (pintype "bidirectional"))
      (node (ref "P14") (pin "P$1") (pinfunction "P$1_P$1") (pintype "bidirectional"))
      (node (ref "U1") (pin "51") (pinfunction "GPIO45_51") (pintype "bidirectional"))
    )
    (net (code "24") (name "B3") (class "Default")
      (node (ref "LCD") (pin "Y19") (pinfunction "B3_Y19") (pintype "bidirectional"))
      (node (ref "P15") (pin "P$1") (pinfunction "P$1_P$1") (pintype "bidirectional"))
      (node (ref "U1") (pin "36") (pinfunction "GP1O48_36") (pintype "bidirectional"))
    )
    (net (code "25") (name "B4") (class "Default")
      (node (ref "LCD") (pin "Y20") (pinfunction "B4_Y20") (pintype "bidirectional"))
      (node (ref "P16") (pin "P$1") (pinfunction "P$1_P$1") (pintype "bidirectional"))
      (node (ref "U1") (pin "37") (pinfunction "GP1O47_37") (pintype "bidirectional"))
    )
    (net (code "26") (name "B5") (class "Default")
      (node (ref "LCD") (pin "Y21") (pinfunction "B5_Y21") (pintype "bidirectional"))
      (node (ref "P1") (pin "P$1") (pinfunction "P$1_P$1") (pintype "bidirectional"))
      (node (ref "U1") (pin "27") (pinfunction "GP1O21_27") (pintype "bidirectional"))
    )
    (net (code "27") (name "BL_PWM") (class "Default")
      (node (ref "P48") (pin "P$1") (pinfunction "P$1_P$1") (pintype "bidirectional"))
      (node (ref "R24") (pin "P$1") (pinfunction "1_P$1") (pintype "bidirectional"))
      (node (ref "U1") (pin "11") (pinfunction "GP1O6_11") (pintype "bidirectional"))
    )
    (net (code "28") (name "DE") (class "Default")
      (node (ref "LCD") (pin "Y13") (pinfunction "DE_Y13") (pintype "bidirectional"))
      (node (ref "P2") (pin "P$1") (pinfunction "P$1_P$1") (pintype "bidirectional"))
      (node (ref "U1") (pin "45") (pinfunction "GP1O40_45") (pintype "bidirectional"))
    )
    (net (code "29") (name "G0") (class "Default")
      (node (ref "LCD") (pin "Y22") (pinfunction "G0_Y22") (pintype "bidirectional"))
      (node (ref "P19") (pin "P$1") (pinfunction "P$1_P$1") (pintype "bidirectional"))
      (node (ref "U1") (pin "19") (pinfunction "GP1O14_19") (pintype "bidirectional"))
    )
    (net (code "30") (name "G1") (class "Default")
      (node (ref "LCD") (pin "Y23") (pinfunction "G1_Y23") (pintype "bidirectional"))
      (node (ref "P18") (pin "P$1") (pinfunction "P$1_P$1") (pintype "bidirectional"))
      (node (ref "U1") (pin "18") (pinfunction "GP1O13_18") (pintype "bidirectional"))
    )
    (net (code "31") (name "G2") (class "Default")
      (node (ref "LCD") (pin "Y24") (pinfunction "G2_Y24") (pintype "bidirectional"))
      (node (ref "P20") (pin "P$1") (pinfunction "P$1_P$1") (pintype "bidirectional"))
      (node (ref "U1") (pin "17") (pinfunction "GP1O12_17") (pintype "bidirectional"))
    )
    (net (code "32") (name "G3") (class "Default")
      (node (ref "LCD") (pin "Y25") (pinfunction "G3_Y25") (pintype "bidirectional"))
      (node (ref "P21") (pin "P$1") (pinfunction "P$1_P$1") (pintype "bidirectional"))
      (node (ref "U1") (pin "16") (pinfunction "GP1O11_16") (pintype "bidirectional"))
    )
    (net (code "33") (name "G4") (class "Default")
      (node (ref "LCD") (pin "Y26") (pinfunction "G4_Y26") (pintype "bidirectional"))
      (node (ref "P22") (pin "P$1") (pinfunction "P$1_P$1") (pintype "bidirectional"))
      (node (ref "U1") (pin "15") (pinfunction "GP1O10_15") (pintype "bidirectional"))
    )
    (net (code "34") (name "G5") (class "Default")
      (node (ref "LCD") (pin "Y27") (pinfunction "G5_Y27") (pintype "bidirectional"))
      (node (ref "P23") (pin "P$1") (pinfunction "P$1_P$1") (pintype "bidirectional"))
      (node (ref "U1") (pin "14") (pinfunction "GP1O9_14") (pintype "bidirectional"))
    )
    (net (code "35") (name "GND") (class "Default")
      (node (ref "ANT") (pin "P$1") (pinfunction "GND_P$1") (pintype "bidirectional"))
      (node (ref "C1") (pin "2") (pinfunction "2_2") (pintype "passive"))
      (node (ref "C10") (pin "2") (pinfunction "2_2") (pintype "passive"))
      (node (ref "C11") (pin "2") (pinfunction "2_2") (pintype "passive"))
      (node (ref "C118") (pin "1") (pinfunction "1_1") (pintype "passive"))
      (node (ref "C12") (pin "1") (pinfunction "1_1") (pintype "passive"))
      (node (ref "C13") (pin "2") (pinfunction "2_2") (pintype "passive"))
      (node (ref "C14") (pin "2") (pinfunction "2_2") (pintype "passive"))
      (node (ref "C15") (pin "2") (pinfunction "2_2") (pintype "passive"))
      (node (ref "C16") (pin "2") (pinfunction "2_2") (pintype "passive"))
      (node (ref "C17") (pin "1") (pinfunction "1_1") (pintype "passive"))
      (node (ref "C18") (pin "1") (pinfunction "1_1") (pintype "passive"))
      (node (ref "C19") (pin "2") (pinfunction "2_2") (pintype "passive"))
      (node (ref "C2") (pin "1") (pinfunction "1_1") (pintype "passive"))
      (node (ref "C20") (pin "1") (pinfunction "1_1") (pintype "passive"))
      (node (ref "C21") (pin "2") (pinfunction "2_2") (pintype "passive"))
      (node (ref "C22") (pin "2") (pinfunction "2_2") (pintype "passive"))
      (node (ref "C23") (pin "2") (pinfunction "2_2") (pintype "passive"))
      (node (ref "C230") (pin "1") (pinfunction "1_1") (pintype "passive"))
      (node (ref "C25") (pin "1") (pinfunction "1_1") (pintype "passive"))
      (node (ref "C26") (pin "2") (pinfunction "2_2") (pintype "passive"))
      (node (ref "C27") (pin "1") (pinfunction "1_1") (pintype "passive"))
      (node (ref "C3") (pin "1") (pinfunction "1_1") (pintype "passive"))
      (node (ref "C36") (pin "1") (pinfunction "1_1") (pintype "passive"))
      (node (ref "C4") (pin "1") (pinfunction "1_1") (pintype "passive"))
      (node (ref "C5") (pin "1") (pinfunction "1_1") (pintype "passive"))
      (node (ref "C6") (pin "2") (pinfunction "2_2") (pintype "passive"))
      (node (ref "C7") (pin "2") (pinfunction "2_2") (pintype "passive"))
      (node (ref "C8") (pin "2") (pinfunction "2_2") (pintype "passive"))
      (node (ref "C9") (pin "2") (pinfunction "2_2") (pintype "passive"))
      (node (ref "J1") (pin "2") (pinfunction "C_2") (pintype "bidirectional"))
      (node (ref "J1") (pin "4") (pinfunction "NC1_4") (pintype "bidirectional"))
      (node (ref "J1") (pin "5") (pinfunction "NC2_5") (pintype "bidirectional"))
      (node (ref "J10") (pin "11") (pinfunction "11_11") (pintype "bidirectional"))
      (node (ref "J10") (pin "12") (pinfunction "12_12") (pintype "bidirectional"))
      (node (ref "J10") (pin "13") (pinfunction "P$1_13") (pintype "bidirectional"))
      (node (ref "J10") (pin "14") (pinfunction "P$2_14") (pintype "bidirectional"))
      (node (ref "K112") (pin "P$2") (pinfunction "P$2_P$2") (pintype "bidirectional"))
      (node (ref "LCD") (pin "41") (pinfunction "GND_41") (pintype "bidirectional"))
      (node (ref "LCD") (pin "42") (pinfunction "GND_42") (pintype "bidirectional"))
      (node (ref "LCD") (pin "Y34") (pinfunction "GND_Y34") (pintype "bidirectional"))
      (node (ref "LCD") (pin "Y4") (pinfunction "GND_Y4") (pintype "bidirectional"))
      (node (ref "P35") (pin "P$1") (pinfunction "P$1_P$1") (pintype "bidirectional"))
      (node (ref "P36") (pin "P$1") (pinfunction "P$1_P$1") (pintype "bidirectional"))
      (node (ref "PWR") (pin "-") (pinfunction "-_-") (pintype "passive"))
      (node (ref "Q3") (pin "2") (pinfunction "E_2") (pintype "passive"))
      (node (ref "R17") (pin "2") (pinfunction "2_2") (pintype "passive"))
      (node (ref "R2") (pin "P$1") (pinfunction "1_P$1") (pintype "bidirectional"))
      (node (ref "R31") (pin "P$1") (pinfunction "1_P$1") (pintype "bidirectional"))
      (node (ref "R34") (pin "2") (pinfunction "2_2") (pintype "passive"))
      (node (ref "R37") (pin "2") (pinfunction "2_2") (pintype "passive"))
      (node (ref "U$19") (pin "P$1") (pinfunction "P$1_P$1") (pintype "bidirectional"))
      (node (ref "U$24") (pin "4") (pinfunction "GND_4") (pintype "bidirectional"))
      (node (ref "U$29") (pin "P$1") (pinfunction "P$1_P$1") (pintype "bidirectional"))
      (node (ref "U$32") (pin "P$1") (pinfunction "P$1_P$1") (pintype "bidirectional"))
      (node (ref "U$9") (pin "P$1") (pinfunction "P$1_P$1") (pintype "bidirectional"))
      (node (ref "U1") (pin "57") (pinfunction "GND_57") (pintype "bidirectional"))
      (node (ref "U2") (pin "2") (pinfunction "GND_2") (pintype "bidirectional"))
      (node (ref "U3") (pin "17") (pinfunction "GND1_17") (pintype "bidirectional"))
      (node (ref "U3") (pin "9") (pinfunction "GND_9") (pintype "bidirectional"))
      (node (ref "Y1") (pin "2") (pinfunction "GND_2") (pintype "passive"))
      (node (ref "Y1") (pin "4") (pinfunction "GND_4") (pintype "passive"))
    )
    (net (code "36") (name "GPIO4") (class "Default")
      (node (ref "J1") (pin "3") (pinfunction "B_3") (pintype "bidirectional"))
      (node (ref "R20") (pin "P$1") (pinfunction "1_P$1") (pintype "bidirectional"))
      (node (ref "U1") (pin "9") (pinfunction "GP1O4_9") (pintype "bidirectional"))
    )
    (net (code "37") (name "GPIO38-SDA") (class "Default")
      (node (ref "LCD") (pin "Y36") (pinfunction "TP_SDA_Y36") (pintype "bidirectional"))
      (node (ref "P30") (pin "P$1") (pinfunction "P$1_P$1") (pintype "bidirectional"))
      (node (ref "Q5") (pin "2") (pinfunction "S_2") (pintype "passive"))
      (node (ref "R14") (pin "P$2") (pinfunction "2_P$2") (pintype "bidirectional"))
      (node (ref "R36") (pin "P$2") (pinfunction "2_P$2") (pintype "bidirectional"))
      (node (ref "U1") (pin "43") (pinfunction "GP1O38_43") (pintype "bidirectional"))
      (node (ref "U3") (pin "16") (pinfunction "SDA_16") (pintype "bidirectional"))
    )
    (net (code "38") (name "GPIO39-SCL") (class "Default")
      (node (ref "LCD") (pin "Y37") (pinfunction "TP_SCL_Y37") (pintype "bidirectional"))
      (node (ref "P31") (pin "P$1") (pinfunction "P$1_P$1") (pintype "bidirectional"))
      (node (ref "Q6") (pin "2") (pinfunction "S_2") (pintype "passive"))
      (node (ref "R29") (pin "P$2") (pinfunction "2_P$2") (pintype "bidirectional"))
      (node (ref "R35") (pin "P$1") (pinfunction "1_P$1") (pintype "bidirectional"))
      (node (ref "U1") (pin "44") (pinfunction "GP1O39_44") (pintype "bidirectional"))
      (node (ref "U3") (pin "15") (pinfunction "SCL_15") (pintype "bidirectional"))
    )
    (net (code "39") (name "HSYNC") (class "Default")
      (node (ref "LCD") (pin "Y15") (pinfunction "HSYNC_Y15") (pintype "bidirectional"))
      (node (ref "P12") (pin "P$1") (pinfunction "P$1_P$1") (pintype "bidirectional"))
      (node (ref "U1") (pin "21") (pinfunction "XTAL_32K_P_21") (pintype "bidirectional"))
    )
    (net (code "40") (name "LCD_CS") (class "Default")
      (node (ref "LCD") (pin "Y11") (pinfunction "CS_Y11") (pintype "bidirectional"))
      (node (ref "P10") (pin "P$1") (pinfunction "P$1_P$1") (pintype "bidirectional"))
      (node (ref "U1") (pin "22") (pinfunction "XTAL_32K_N_22") (pintype "bidirectional"))
    )
    (net (code "41") (name "LCD_LEDA") (class "Default")
      (node (ref "C25") (pin "2") (pinfunction "2_2") (pintype "passive"))
      (node (ref "LCD") (pin "Y1") (pinfunction "LEDA_Y1") (pintype "bidirectional"))
      (node (ref "P4") (pin "P$1") (pinfunction "P$1_P$1") (pintype "bidirectional"))
      (node (ref "R23") (pin "2") (pinfunction "2_2") (pintype "passive"))
    )
    (net (code "42") (name "LCD_LEDK") (class "Default")
      (node (ref "LCD") (pin "Y2") (pinfunction "LEDK_Y2") (pintype "bidirectional"))
      (node (ref "LCD") (pin "Y3") (pinfunction "LEDK_Y3") (pintype "bidirectional"))
      (node (ref "P5") (pin "P$1") (pinfunction "P$1_P$1") (pintype "bidirectional"))
      (node (ref "Q3") (pin "3") (pinfunction "C_3") (pintype "passive"))
    )
    (net (code "43") (name "LCD_RST") (class "Default")
      (node (ref "LCD") (pin "Y6") (pinfunction "RESET_Y6") (pintype "bidirectional"))
      (node (ref "P7") (pin "P$1") (pinfunction "P$1_P$1") (pintype "bidirectional"))
      (node (ref "U3") (pin "10") (pinfunction "P4_10") (pintype "bidirectional"))
    )
    (net (code "44") (name "LCD_SCK") (class "Default")
      (node (ref "LCD") (pin "Y10") (pinfunction "SCK_Y10") (pintype "bidirectional"))
      (node (ref "P9") (pin "P$1") (pinfunction "P$1_P$1") (pintype "bidirectional"))
      (node (ref "U1") (pin "7") (pinfunction "GP1O2_7") (pintype "bidirectional"))
    )
    (net (code "45") (name "LCD_SDA") (class "Default")
      (node (ref "LCD") (pin "Y9") (pinfunction "SDA_Y9") (pintype "bidirectional"))
      (node (ref "P8") (pin "P$1") (pinfunction "P$1_P$1") (pintype "bidirectional"))
      (node (ref "U1") (pin "6") (pinfunction "GP1O1_6") (pintype "bidirectional"))
    )
    (net (code "46") (name "Net-(ANT-ANT)") (class "Default")
      (node (ref "ANT") (pin "P$2") (pinfunction "ANT_P$2") (pintype "bidirectional"))
      (node (ref "C2") (pin "2") (pinfunction "2_2") (pintype "passive"))
      (node (ref "R6") (pin "P$1") (pinfunction "1_P$1") (pintype "bidirectional"))
    )
    (net (code "47") (name "Net-(Q3-B)") (class "Default")
      (node (ref "Q3") (pin "1") (pinfunction "B_1") (pintype "passive"))
      (node (ref "R2") (pin "P$2") (pinfunction "2_P$2") (pintype "bidirectional"))
      (node (ref "R24") (pin "P$2") (pinfunction "2_P$2") (pintype "bidirectional"))
    )
    (net (code "48") (name "Net-(R6-2)") (class "Default")
      (node (ref "C4") (pin "2") (pinfunction "2_2") (pintype "passive"))
      (node (ref "R6") (pin "P$2") (pinfunction "2_P$2") (pintype "bidirectional"))
      (node (ref "U1") (pin "1") (pinfunction "LNA_IN_1") (pintype "bidirectional"))
    )
    (net (code "49") (name "Net-(R10-1)") (class "Default")
      (node (ref "PWR") (pin "+") (pinfunction "+_+") (pintype "passive"))
      (node (ref "R10") (pin "P$1") (pinfunction "1_P$1") (pintype "bidirectional"))
    )
    (net (code "50") (name "Net-(R31-2)") (class "Default")
      (node (ref "P47") (pin "P$1") (pinfunction "P$1_P$1") (pintype "bidirectional"))
      (node (ref "R31") (pin "P$2") (pinfunction "2_P$2") (pintype "bidirectional"))
      (node (ref "R40") (pin "P$1") (pinfunction "1_P$1") (pintype "bidirectional"))
      (node (ref "U2") (pin "5") (pinfunction "BF_5") (pintype "bidirectional"))
    )
    (net (code "51") (name "Net-(U$24-CLK)") (class "Default")
      (node (ref "U$24") (pin "6") (pinfunction "CLK_6") (pintype "bidirectional"))
      (node (ref "U1") (pin "33") (pinfunction "SPICLK_33") (pintype "bidirectional"))
    )
    (net (code "52") (name "Net-(U$24-DIMO)") (class "Default")
      (node (ref "U$24") (pin "5") (pinfunction "DIMO_5") (pintype "input"))
      (node (ref "U1") (pin "35") (pinfunction "SPI_MOSI_35") (pintype "bidirectional"))
    )
    (net (code "53") (name "Net-(U$24-{slash}HOLD)") (class "Default")
      (node (ref "U$24") (pin "7") (pinfunction "/HOLD_7") (pintype "bidirectional"))
      (node (ref "U1") (pin "30") (pinfunction "SPIHD_30") (pintype "bidirectional"))
    )
    (net (code "54") (name "Net-(U1-GP1O19{slash}USB_D-)") (class "Default")
      (node (ref "R43") (pin "2") (pinfunction "2_2") (pintype "passive"))
      (node (ref "U1") (pin "25") (pinfunction "GP1O19/USB_D-_25") (pintype "bidirectional"))
    )
    (net (code "55") (name "Net-(U1-GP1O20{slash}USB_D+)") (class "Default")
      (node (ref "R44") (pin "2") (pinfunction "2_2") (pintype "passive"))
      (node (ref "U1") (pin "26") (pinfunction "GP1O20/USB_D+_26") (pintype "bidirectional"))
    )
    (net (code "56") (name "Net-(U1-XTAL_N)") (class "Default")
      (node (ref "C9") (pin "1") (pinfunction "1_1") (pintype "passive"))
      (node (ref "U1") (pin "54") (pinfunction "XTAL_N_54") (pintype "bidirectional"))
      (node (ref "Y1") (pin "1") (pinfunction "C1_1") (pintype "passive"))
    )
    (net (code "57") (name "Net-(U1-XTAL_P)") (class "Default")
      (node (ref "C13") (pin "1") (pinfunction "1_1") (pintype "passive"))
      (node (ref "U1") (pin "53") (pinfunction "XTAL_P_53") (pintype "bidirectional"))
      (node (ref "Y1") (pin "3") (pinfunction "C2_3") (pintype "passive"))
    )
    (net (code "58") (name "Net-(U2-LX)") (class "Default")
      (node (ref "L3") (pin "1") (pinfunction "1_1") (pintype "passive"))
      (node (ref "U2") (pin "3") (pinfunction "LX_3") (pintype "bidirectional"))
    )
    (net (code "59") (name "Net-(U3-A0)") (class "Default")
      (node (ref "R22") (pin "1") (pinfunction "1_1") (pintype "passive"))
      (node (ref "U3") (pin "2") (pinfunction "A0_2") (pintype "bidirectional"))
    )
    (net (code "60") (name "Net-(U3-A1)") (class "Default")
      (node (ref "R34") (pin "1") (pinfunction "1_1") (pintype "passive"))
      (node (ref "U3") (pin "3") (pinfunction "A1_3") (pintype "bidirectional"))
    )
    (net (code "61") (name "Net-(U3-A2)") (class "Default")
      (node (ref "R37") (pin "1") (pinfunction "1_1") (pintype "passive"))
      (node (ref "U3") (pin "4") (pinfunction "A2_4") (pintype "bidirectional"))
    )
    (net (code "62") (name "Net-(U3-INT)") (class "Default")
      (node (ref "R18") (pin "2") (pinfunction "2_2") (pintype "passive"))
      (node (ref "U3") (pin "14") (pinfunction "INT_14") (pintype "bidirectional"))
    )
    (net (code "63") (name "PCLK") (class "Default")
      (node (ref "LCD") (pin "Y12") (pinfunction "PLCK_Y12") (pintype "bidirectional"))
      (node (ref "P11") (pin "P$1") (pinfunction "P$1_P$1") (pintype "bidirectional"))
      (node (ref "U1") (pin "47") (pinfunction "GP1O41_47") (pintype "bidirectional"))
    )
    (net (code "64") (name "R1") (class "Default")
      (node (ref "LCD") (pin "Y29") (pinfunction "R1_Y29") (pintype "bidirectional"))
      (node (ref "P24") (pin "P$1") (pinfunction "P$1_P$1") (pintype "bidirectional"))
      (node (ref "U1") (pin "52") (pinfunction "GPIO46_52") (pintype "bidirectional"))
    )
    (net (code "65") (name "R2") (class "Default")
      (node (ref "LCD") (pin "Y30") (pinfunction "R2_Y30") (pintype "bidirectional"))
      (node (ref "P17") (pin "P$1") (pinfunction "P$1_P$1") (pintype "bidirectional"))
      (node (ref "U1") (pin "8") (pinfunction "GP1O3_8") (pintype "bidirectional"))
    )
    (net (code "66") (name "R3") (class "Default")
      (node (ref "LCD") (pin "Y31") (pinfunction "R3_Y31") (pintype "bidirectional"))
      (node (ref "P26") (pin "P$1") (pinfunction "P$1_P$1") (pintype "bidirectional"))
      (node (ref "U1") (pin "13") (pinfunction "GP1O8_13") (pintype "bidirectional"))
    )
    (net (code "67") (name "R4") (class "Default")
      (node (ref "LCD") (pin "Y32") (pinfunction "R4_Y32") (pintype "bidirectional"))
      (node (ref "P27") (pin "P$1") (pinfunction "P$1_P$1") (pintype "bidirectional"))
      (node (ref "U1") (pin "24") (pinfunction "GP1O18_24") (pintype "bidirectional"))
    )
    (net (code "68") (name "R5") (class "Default")
      (node (ref "LCD") (pin "Y33") (pinfunction "R5_Y33") (pintype "bidirectional"))
      (node (ref "P28") (pin "P$1") (pinfunction "P$1_P$1") (pintype "bidirectional"))
      (node (ref "U1") (pin "23") (pinfunction "GP1O17_23") (pintype "bidirectional"))
    )
    (net (code "69") (name "TP_INT") (class "Default")
      (node (ref "LCD") (pin "Y35") (pinfunction "TP_INT_Y35") (pintype "bidirectional"))
      (node (ref "P25") (pin "P$1") (pinfunction "P$1_P$1") (pintype "bidirectional"))
      (node (ref "R3") (pin "1") (pinfunction "1_1") (pintype "passive"))
      (node (ref "U3") (pin "7") (pinfunction "P2_7") (pintype "bidirectional"))
    )
    (net (code "70") (name "TP_RST") (class "Default")
      (node (ref "LCD") (pin "Y38") (pinfunction "TP_RESET_Y38") (pintype "bidirectional"))
      (node (ref "P32") (pin "P$1") (pinfunction "P$1_P$1") (pintype "bidirectional"))
      (node (ref "R13") (pin "P$2") (pinfunction "2_P$2") (pintype "bidirectional"))
      (node (ref "U3") (pin "5") (pinfunction "P0_5") (pintype "bidirectional"))
    )
    (net (code "71") (name "VDD_3.3V") (class "Default")
      (node (ref "C12") (pin "2") (pinfunction "2_2") (pintype "passive"))
      (node (ref "C14") (pin "1") (pinfunction "1_1") (pintype "passive"))
      (node (ref "C21") (pin "1") (pinfunction "1_1") (pintype "passive"))
      (node (ref "C22") (pin "1") (pinfunction "1_1") (pintype "passive"))
      (node (ref "C23") (pin "1") (pinfunction "1_1") (pintype "passive"))
      (node (ref "C230") (pin "2") (pinfunction "2_2") (pintype "passive"))
      (node (ref "C3") (pin "2") (pinfunction "2_2") (pintype "passive"))
      (node (ref "C36") (pin "2") (pinfunction "2_2") (pintype "passive"))
      (node (ref "C6") (pin "1") (pinfunction "1_1") (pintype "passive"))
      (node (ref "C7") (pin "1") (pinfunction "1_1") (pintype "passive"))
      (node (ref "C8") (pin "1") (pinfunction "1_1") (pintype "passive"))
      (node (ref "L2") (pin "1") (pinfunction "1_1") (pintype "passive"))
      (node (ref "L3") (pin "2") (pinfunction "2_2") (pintype "passive"))
      (node (ref "LCD") (pin "Y39") (pinfunction "VCC_Y39") (pintype "bidirectional"))
      (node (ref "P6") (pin "P$1") (pinfunction "P$1_P$1") (pintype "bidirectional"))
      (node (ref "Q1") (pin "2") (pinfunction "S_2") (pintype "bidirectional"))
      (node (ref "Q5") (pin "1") (pinfunction "G_1") (pintype "passive"))
      (node (ref "Q6") (pin "1") (pinfunction "G_1") (pintype "passive"))
      (node (ref "Q8") (pin "1") (pinfunction "G_1") (pintype "passive"))
      (node (ref "Q9") (pin "1") (pinfunction "G_1") (pintype "passive"))
      (node (ref "R1") (pin "P$2") (pinfunction "2_P$2") (pintype "bidirectional"))
      (node (ref "R10") (pin "P$2") (pinfunction "2_P$2") (pintype "bidirectional"))
      (node (ref "R13") (pin "P$1") (pinfunction "1_P$1") (pintype "bidirectional"))
      (node (ref "R14") (pin "P$1") (pinfunction "1_P$1") (pintype "bidirectional"))
      (node (ref "R16") (pin "2") (pinfunction "2_2") (pintype "passive"))
      (node (ref "R18") (pin "1") (pinfunction "1_1") (pintype "passive"))
      (node (ref "R19") (pin "P$2") (pinfunction "2_P$2") (pintype "bidirectional"))
      (node (ref "R20") (pin "P$2") (pinfunction "2_P$2") (pintype "bidirectional"))
      (node (ref "R21") (pin "P$2") (pinfunction "2_P$2") (pintype "bidirectional"))
      (node (ref "R22") (pin "2") (pinfunction "2_2") (pintype "passive"))
      (node (ref "R23") (pin "1") (pinfunction "1_1") (pintype "passive"))
      (node (ref "R29") (pin "P$1") (pinfunction "1_P$1") (pintype "bidirectional"))
      (node (ref "R3") (pin "2") (pinfunction "2_2") (pintype "passive"))
      (node (ref "R35") (pin "P$2") (pinfunction "2_P$2") (pintype "bidirectional"))
      (node (ref "R36") (pin "P$1") (pinfunction "1_P$1") (pintype "bidirectional"))
      (node (ref "R38") (pin "P$2") (pinfunction "2_P$2") (pintype "bidirectional"))
      (node (ref "R39") (pin "P$1") (pinfunction "1_P$1") (pintype "bidirectional"))
      (node (ref "R40") (pin "P$2") (pinfunction "2_P$2") (pintype "bidirectional"))
      (node (ref "R50") (pin "P$1") (pinfunction "1_P$1") (pintype "bidirectional"))
      (node (ref "U1") (pin "46") (pinfunction "VDD3P3_CPU_46") (pintype "bidirectional"))
      (node (ref "U1") (pin "55") (pinfunction "VDDA_55") (pintype "bidirectional"))
      (node (ref "U1") (pin "56") (pinfunction "VDDA_56") (pintype "bidirectional"))
      (node (ref "U3") (pin "1") (pinfunction "VCC_1") (pintype "bidirectional"))
    )
    (net (code "72") (name "VDD_LCD") (class "Default")
      (node (ref "C10") (pin "1") (pinfunction "1_1") (pintype "passive"))
      (node (ref "C11") (pin "1") (pinfunction "1_1") (pintype "passive"))
      (node (ref "LCD") (pin "Y5") (pinfunction "VCC_Y5") (pintype "bidirectional"))
      (node (ref "P34") (pin "P$1") (pinfunction "P$1_P$1") (pintype "bidirectional"))
      (node (ref "Q1") (pin "3") (pinfunction "D_3") (pintype "bidirectional"))
    )
    (net (code "73") (name "VSYNC") (class "Default")
      (node (ref "LCD") (pin "Y14") (pinfunction "VSYNC_Y14") (pintype "bidirectional"))
      (node (ref "P3") (pin "P$1") (pinfunction "P$1_P$1") (pintype "bidirectional"))
      (node (ref "U1") (pin "12") (pinfunction "GP1O7_12") (pintype "bidirectional"))
    )
    (net (code "74") (name "unconnected-(LCD-B0-PadY16)") (class "Default")
      (node (ref "LCD") (pin "Y16") (pinfunction "B0_Y16") (pintype "bidirectional"))
    )
    (net (code "75") (name "unconnected-(LCD-NC-PadY7)") (class "Default")
      (node (ref "LCD") (pin "Y7") (pinfunction "NC_Y7") (pintype "bidirectional"))
    )
    (net (code "76") (name "unconnected-(LCD-NC-PadY8)") (class "Default")
      (node (ref "LCD") (pin "Y8") (pinfunction "NC_Y8") (pintype "bidirectional"))
    )
    (net (code "77") (name "unconnected-(LCD-R0-PadY28)") (class "Default")
      (node (ref "LCD") (pin "Y28") (pinfunction "R0_Y28") (pintype "bidirectional"))
    )
    (net (code "78") (name "unconnected-(U$30-PadP$1)") (class "Default")
      (node (ref "U$30") (pin "P$1") (pinfunction "P$1_P$1") (pintype "bidirectional"))
    )
    (net (code "79") (name "unconnected-(U1-GP1O33-Pad38)") (class "Default")
      (node (ref "U1") (pin "38") (pinfunction "GP1O33_38") (pintype "bidirectional"))
    )
    (net (code "80") (name "unconnected-(U1-GP1O34-Pad39)") (class "Default")
      (node (ref "U1") (pin "39") (pinfunction "GP1O34_39") (pintype "bidirectional"))
    )
    (net (code "81") (name "unconnected-(U1-GP1O35-Pad40)") (class "Default")
      (node (ref "U1") (pin "40") (pinfunction "GP1O35_40") (pintype "bidirectional"))
    )
    (net (code "82") (name "unconnected-(U1-GP1O36-Pad41)") (class "Default")
      (node (ref "U1") (pin "41") (pinfunction "GP1O36_41") (pintype "bidirectional"))
    )
    (net (code "83") (name "unconnected-(U1-GP1O37-Pad42)") (class "Default")
      (node (ref "U1") (pin "42") (pinfunction "GP1O37_42") (pintype "bidirectional"))
    )
    (net (code "84") (name "unconnected-(U1-SPICS1-Pad28)") (class "Default")
      (node (ref "U1") (pin "28") (pinfunction "SPICS1_28") (pintype "bidirectional"))
    )
    (net (code "85") (name "unconnected-(U3-P6-Pad12)") (class "Default")
      (node (ref "U3") (pin "12") (pinfunction "P6_12") (pintype "bidirectional"))
    )
    (net (code "86") (name "unconnected-(U3-P7-Pad13)") (class "Default")
      (node (ref "U3") (pin "13") (pinfunction "P7_13") (pintype "bidirectional"))
    )
  )
)
